# SMPS.net
KiCad netlist of a schematic drawn in Altium Designer
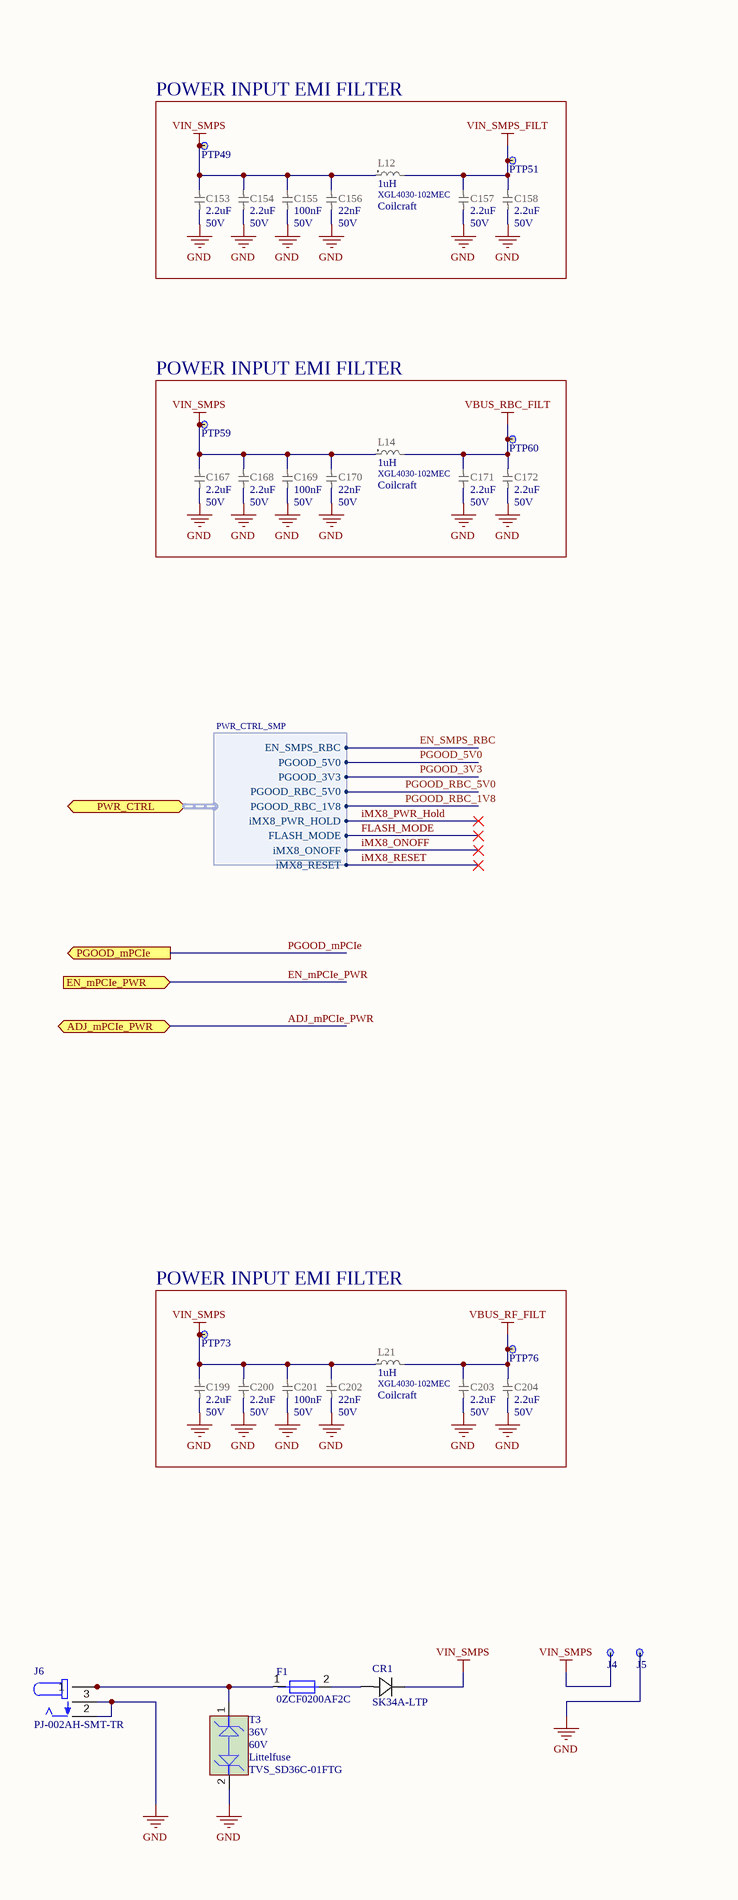
[diagram p0: SMPS.SchDoc, left]
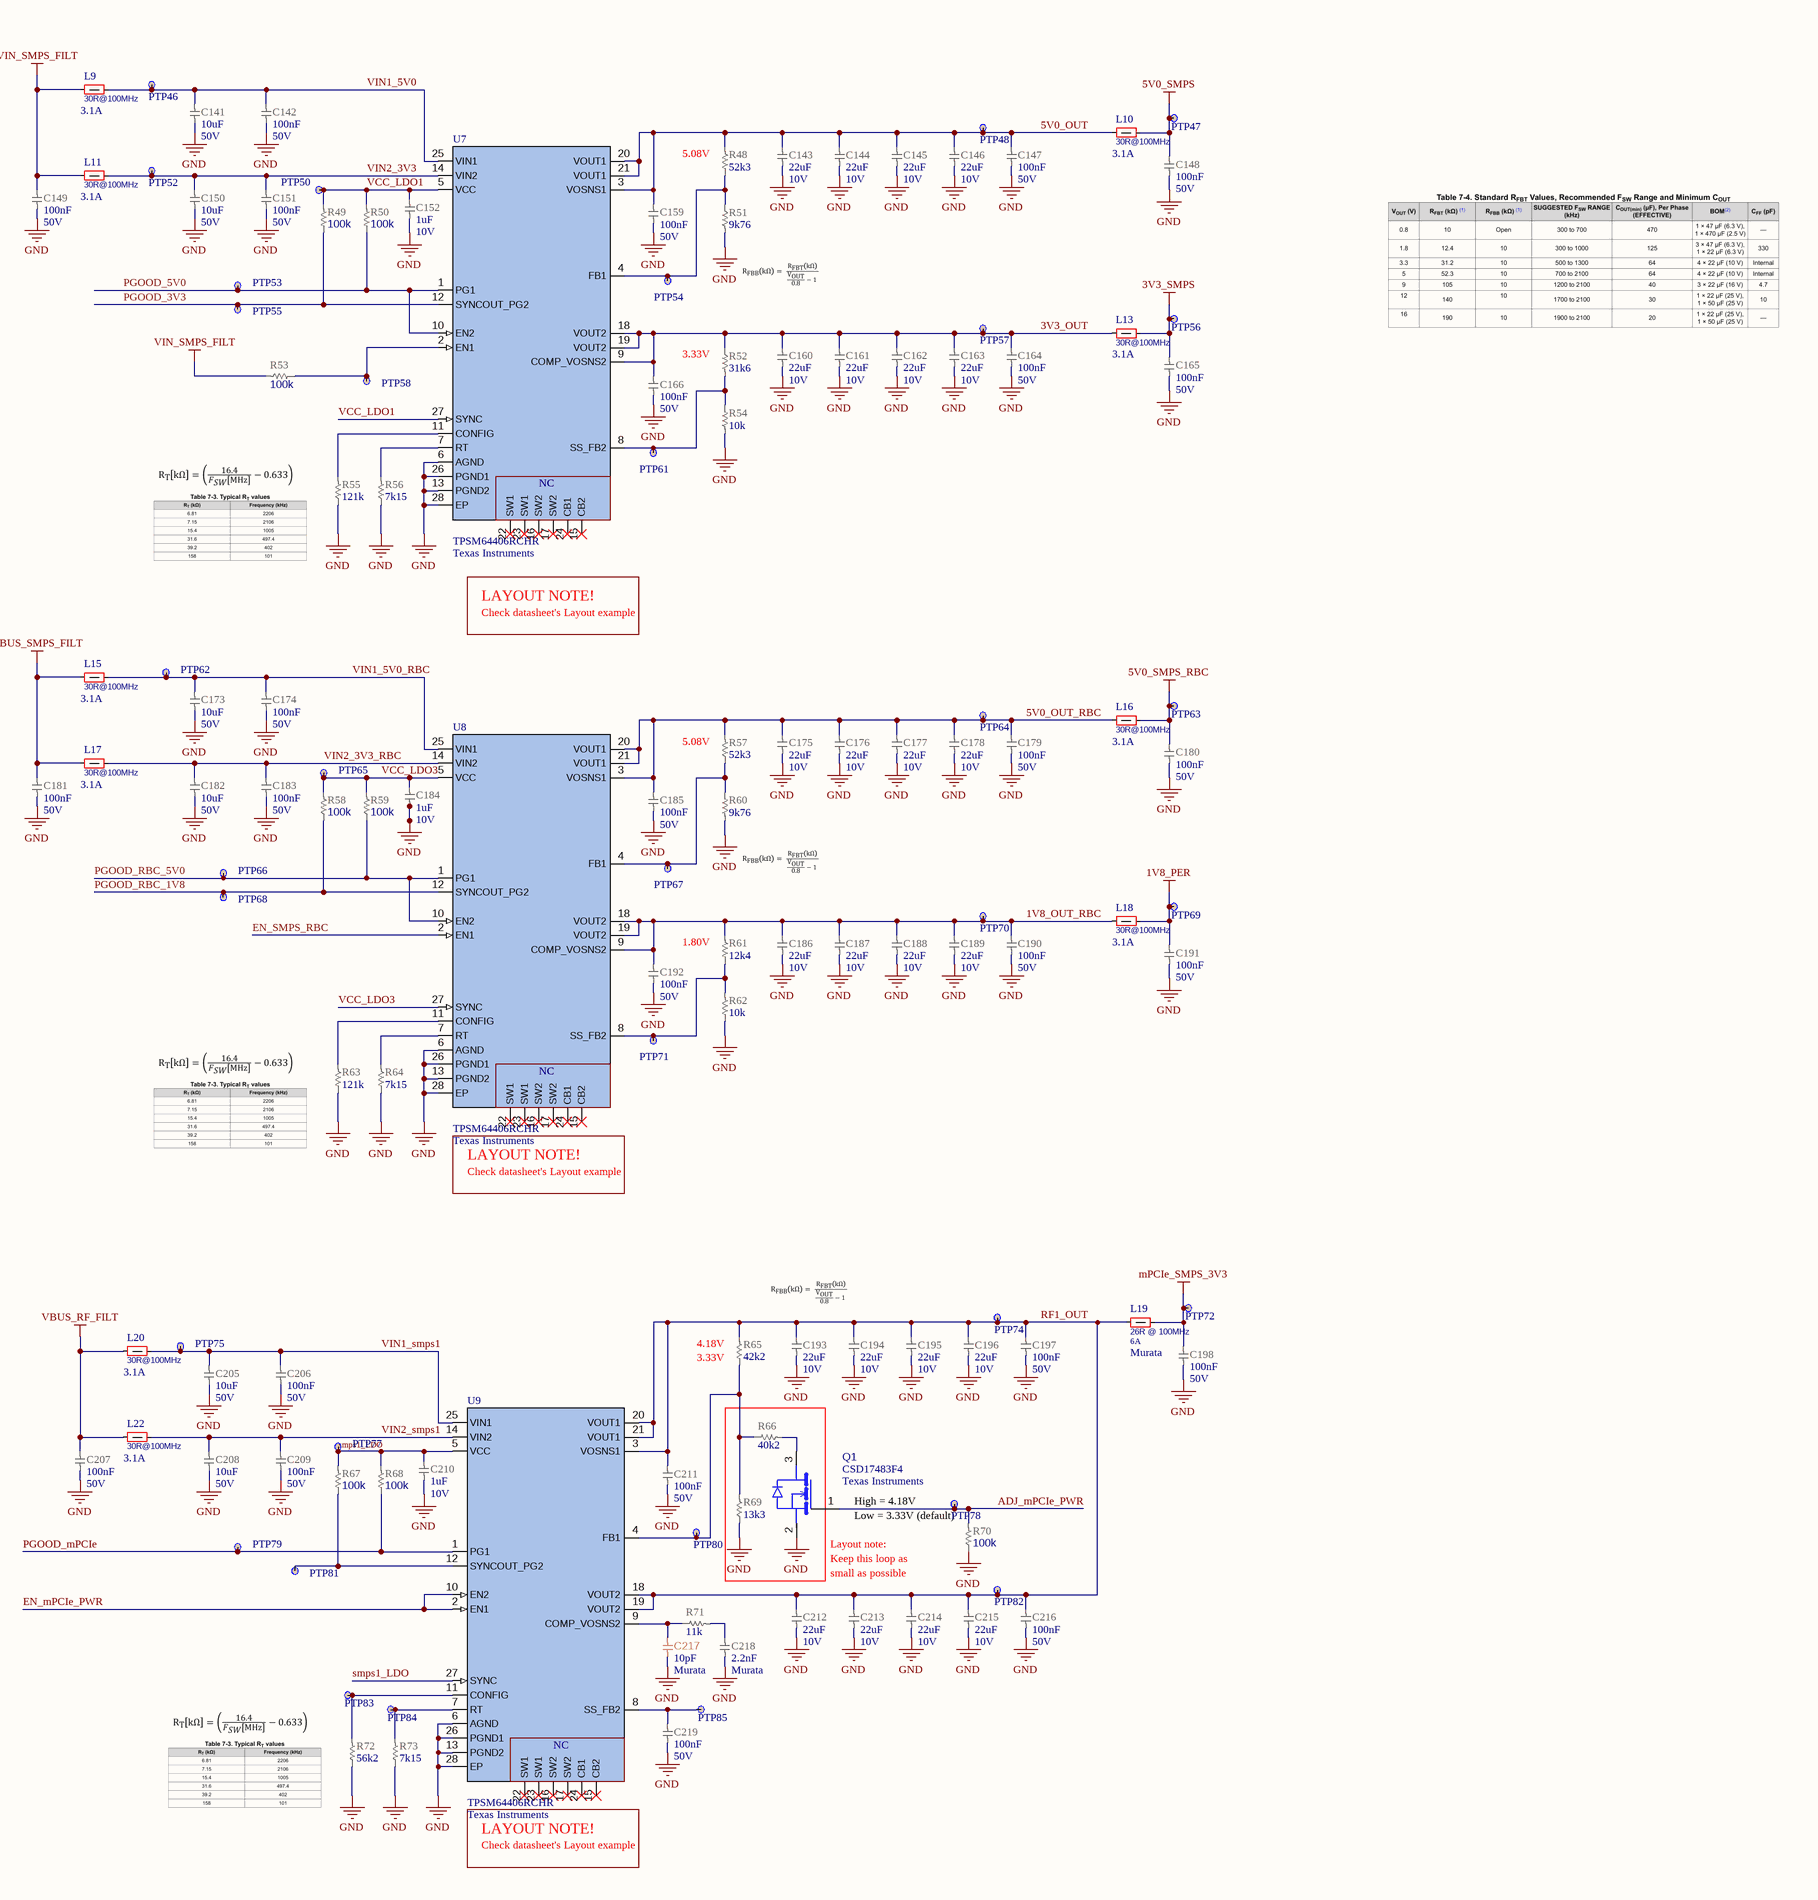
[diagram p1: SMPS.SchDoc, right]

(export (version "E")
  (design (tool "Eeschema 10.0.6"))
  (components
    (comp (ref "C141")
      (value "10uF")
      (footprint "CAP_1206_UN1Q")
      (description "CAP")
      (fields
        (field (name "PART NUMBER") "CL31B106KBHNNNE")
        (field (name "MANUFACTURER") "Samsung")
        (field (name "VOLTAGE") "50V")
      )
      (libsource (lib "robo_cam") (part "CMP-001-000368-12"))
    )
    (comp (ref "C142")
      (value "100nF")
      (footprint "CAP_0402_UN1Q")
      (description "CAP")
      (fields
        (field (name "PART NUMBER") "GRM155R71H104KE14D")
        (field (name "MANUFACTURER") "Murata")
        (field (name "VOLTAGE") "50V")
      )
      (libsource (lib "robo_cam") (part "CMP-001-000371-14"))
    )
    (comp (ref "C143")
      (value "22uF")
      (footprint "CAP_0805_UN1Q")
      (description "CAP")
      (fields
        (field (name "VOLTAGE") "10V")
        (field (name "TOLERANCE") "+/-20%")
        (field (name "PART NUMBER") "GRM21BZ71A226ME15L")
      )
      (libsource (lib "robo_cam") (part "CMP-001-000892-11"))
    )
    (comp (ref "C144")
      (value "22uF")
      (footprint "CAP_0805_UN1Q")
      (description "CAP")
      (fields
        (field (name "VOLTAGE") "10V")
        (field (name "TOLERANCE") "+/-20%")
        (field (name "PART NUMBER") "GRM21BZ71A226ME15L")
      )
      (libsource (lib "robo_cam") (part "CMP-001-000892-11"))
    )
    (comp (ref "C145")
      (value "22uF")
      (footprint "CAP_0805_UN1Q")
      (description "CAP")
      (fields
        (field (name "VOLTAGE") "10V")
        (field (name "TOLERANCE") "+/-20%")
        (field (name "PART NUMBER") "GRM21BZ71A226ME15L")
      )
      (libsource (lib "robo_cam") (part "CMP-001-000892-11"))
    )
    (comp (ref "C146")
      (value "22uF")
      (footprint "CAP_0805_UN1Q")
      (description "CAP")
      (fields
        (field (name "VOLTAGE") "10V")
        (field (name "TOLERANCE") "+/-20%")
        (field (name "PART NUMBER") "GRM21BZ71A226ME15L")
      )
      (libsource (lib "robo_cam") (part "CMP-001-000892-11"))
    )
    (comp (ref "C147")
      (value "100nF")
      (footprint "CAP_0402_UN1Q")
      (description "CAP")
      (fields
        (field (name "PART NUMBER") "GRM155R71H104KE14D")
        (field (name "MANUFACTURER") "Murata")
        (field (name "VOLTAGE") "50V")
      )
      (libsource (lib "robo_cam") (part "CMP-001-000371-14"))
    )
    (comp (ref "C148")
      (value "100nF")
      (footprint "CAP_0402_UN1Q")
      (description "CAP")
      (fields
        (field (name "PART NUMBER") "GRM155R71H104KE14D")
        (field (name "MANUFACTURER") "Murata")
        (field (name "VOLTAGE") "50V")
      )
      (libsource (lib "robo_cam") (part "CMP-001-000371-14"))
    )
    (comp (ref "C149")
      (value "100nF")
      (footprint "CAP_0402_UN1Q")
      (description "CAP")
      (fields
        (field (name "PART NUMBER") "GRM155R71H104KE14D")
        (field (name "MANUFACTURER") "Murata")
        (field (name "VOLTAGE") "50V")
      )
      (libsource (lib "robo_cam") (part "CMP-001-000371-14"))
    )
    (comp (ref "C150")
      (value "10uF")
      (footprint "CAP_1206_UN1Q")
      (description "CAP")
      (fields
        (field (name "PART NUMBER") "CL31B106KBHNNNE")
        (field (name "MANUFACTURER") "Samsung")
        (field (name "VOLTAGE") "50V")
      )
      (libsource (lib "robo_cam") (part "CMP-001-000368-12"))
    )
    (comp (ref "C151")
      (value "100nF")
      (footprint "CAP_0402_UN1Q")
      (description "CAP")
      (fields
        (field (name "PART NUMBER") "GRM155R71H104KE14D")
        (field (name "MANUFACTURER") "Murata")
        (field (name "VOLTAGE") "50V")
      )
      (libsource (lib "robo_cam") (part "CMP-001-000371-14"))
    )
    (comp (ref "C152")
      (value "1uF")
      (footprint "CAP_0201_UN1Q")
      (description "CAP")
      (fields
        (field (name "PART NUMBER") "KGM03CS61A105MH")
        (field (name "MANUFACTURER") "Kyocera")
        (field (name "VOLTAGE") "10V")
      )
      (libsource (lib "robo_cam") (part "CMP-001-000336-15"))
    )
    (comp (ref "C153")
      (value "2.2uF")
      (footprint "CAP_0805_UN1Q")
      (description "CAP")
      (fields
        (field (name "MANUFACTURER") "TDK")
        (field (name "PART NUMBER") "C2012X7R1H225K125AC")
        (field (name "VOLTAGE") "50V")
      )
      (libsource (lib "robo_cam") (part "CMP-001-000383-12"))
    )
    (comp (ref "C154")
      (value "2.2uF")
      (footprint "CAP_0805_UN1Q")
      (description "CAP")
      (fields
        (field (name "MANUFACTURER") "TDK")
        (field (name "PART NUMBER") "C2012X7R1H225K125AC")
        (field (name "VOLTAGE") "50V")
      )
      (libsource (lib "robo_cam") (part "CMP-001-000383-12"))
    )
    (comp (ref "C155")
      (value "100nF")
      (footprint "CAP_0402_UN1Q")
      (description "CAP")
      (fields
        (field (name "PART NUMBER") "GRM155R71H104KE14D")
        (field (name "MANUFACTURER") "Murata")
        (field (name "VOLTAGE") "50V")
      )
      (libsource (lib "robo_cam") (part "CMP-001-000371-14"))
    )
    (comp (ref "C156")
      (value "22nF")
      (footprint "CAP_0402_UN1Q")
      (description "CAP")
      (fields
        (field (name "VOLTAGE") "50V")
        (field (name "PART NUMBER") "GCM155R71H223KA55D")
        (field (name "TOLERANCE") "+/-10%")
      )
      (libsource (lib "robo_cam") (part "CMP-001-000321-12"))
    )
    (comp (ref "C157")
      (value "2.2uF")
      (footprint "CAP_0805_UN1Q")
      (description "CAP")
      (fields
        (field (name "MANUFACTURER") "TDK")
        (field (name "PART NUMBER") "C2012X7R1H225K125AC")
        (field (name "VOLTAGE") "50V")
      )
      (libsource (lib "robo_cam") (part "CMP-001-000383-12"))
    )
    (comp (ref "C158")
      (value "2.2uF")
      (footprint "CAP_0805_UN1Q")
      (description "CAP")
      (fields
        (field (name "MANUFACTURER") "TDK")
        (field (name "PART NUMBER") "C2012X7R1H225K125AC")
        (field (name "VOLTAGE") "50V")
      )
      (libsource (lib "robo_cam") (part "CMP-001-000383-12"))
    )
    (comp (ref "C159")
      (value "100nF")
      (footprint "CAP_0402_UN1Q")
      (description "CAP")
      (fields
        (field (name "PART NUMBER") "GRM155R71H104KE14D")
        (field (name "MANUFACTURER") "Murata")
        (field (name "VOLTAGE") "50V")
      )
      (libsource (lib "robo_cam") (part "CMP-001-000371-14"))
    )
    (comp (ref "C160")
      (value "22uF")
      (footprint "CAP_0805_UN1Q")
      (description "CAP")
      (fields
        (field (name "VOLTAGE") "10V")
        (field (name "TOLERANCE") "+/-20%")
        (field (name "PART NUMBER") "GRM21BZ71A226ME15L")
      )
      (libsource (lib "robo_cam") (part "CMP-001-000892-11"))
    )
    (comp (ref "C161")
      (value "22uF")
      (footprint "CAP_0805_UN1Q")
      (description "CAP")
      (fields
        (field (name "VOLTAGE") "10V")
        (field (name "TOLERANCE") "+/-20%")
        (field (name "PART NUMBER") "GRM21BZ71A226ME15L")
      )
      (libsource (lib "robo_cam") (part "CMP-001-000892-11"))
    )
    (comp (ref "C162")
      (value "22uF")
      (footprint "CAP_0805_UN1Q")
      (description "CAP")
      (fields
        (field (name "VOLTAGE") "10V")
        (field (name "TOLERANCE") "+/-20%")
        (field (name "PART NUMBER") "GRM21BZ71A226ME15L")
      )
      (libsource (lib "robo_cam") (part "CMP-001-000892-11"))
    )
    (comp (ref "C163")
      (value "22uF")
      (footprint "CAP_0805_UN1Q")
      (description "CAP")
      (fields
        (field (name "VOLTAGE") "10V")
        (field (name "TOLERANCE") "+/-20%")
        (field (name "PART NUMBER") "GRM21BZ71A226ME15L")
      )
      (libsource (lib "robo_cam") (part "CMP-001-000892-11"))
    )
    (comp (ref "C164")
      (value "100nF")
      (footprint "CAP_0402_UN1Q")
      (description "CAP")
      (fields
        (field (name "PART NUMBER") "GRM155R71H104KE14D")
        (field (name "MANUFACTURER") "Murata")
        (field (name "VOLTAGE") "50V")
      )
      (libsource (lib "robo_cam") (part "CMP-001-000371-14"))
    )
    (comp (ref "C165")
      (value "100nF")
      (footprint "CAP_0402_UN1Q")
      (description "CAP")
      (fields
        (field (name "PART NUMBER") "GRM155R71H104KE14D")
        (field (name "MANUFACTURER") "Murata")
        (field (name "VOLTAGE") "50V")
      )
      (libsource (lib "robo_cam") (part "CMP-001-000371-14"))
    )
    (comp (ref "C166")
      (value "100nF")
      (footprint "CAP_0402_UN1Q")
      (description "CAP")
      (fields
        (field (name "PART NUMBER") "GRM155R71H104KE14D")
        (field (name "MANUFACTURER") "Murata")
        (field (name "VOLTAGE") "50V")
      )
      (libsource (lib "robo_cam") (part "CMP-001-000371-14"))
    )
    (comp (ref "C167")
      (value "2.2uF")
      (footprint "CAP_0805_UN1Q")
      (description "CAP")
      (fields
        (field (name "MANUFACTURER") "TDK")
        (field (name "PART NUMBER") "C2012X7R1H225K125AC")
        (field (name "VOLTAGE") "50V")
      )
      (libsource (lib "robo_cam") (part "CMP-001-000383-12"))
    )
    (comp (ref "C168")
      (value "2.2uF")
      (footprint "CAP_0805_UN1Q")
      (description "CAP")
      (fields
        (field (name "MANUFACTURER") "TDK")
        (field (name "PART NUMBER") "C2012X7R1H225K125AC")
        (field (name "VOLTAGE") "50V")
      )
      (libsource (lib "robo_cam") (part "CMP-001-000383-12"))
    )
    (comp (ref "C169")
      (value "100nF")
      (footprint "CAP_0402_UN1Q")
      (description "CAP")
      (fields
        (field (name "PART NUMBER") "GRM155R71H104KE14D")
        (field (name "MANUFACTURER") "Murata")
        (field (name "VOLTAGE") "50V")
      )
      (libsource (lib "robo_cam") (part "CMP-001-000371-14"))
    )
    (comp (ref "C170")
      (value "22nF")
      (footprint "CAP_0402_UN1Q")
      (description "CAP")
      (fields
        (field (name "VOLTAGE") "50V")
        (field (name "PART NUMBER") "GCM155R71H223KA55D")
        (field (name "TOLERANCE") "+/-10%")
      )
      (libsource (lib "robo_cam") (part "CMP-001-000321-12"))
    )
    (comp (ref "C171")
      (value "2.2uF")
      (footprint "CAP_0805_UN1Q")
      (description "CAP")
      (fields
        (field (name "MANUFACTURER") "TDK")
        (field (name "PART NUMBER") "C2012X7R1H225K125AC")
        (field (name "VOLTAGE") "50V")
      )
      (libsource (lib "robo_cam") (part "CMP-001-000383-12"))
    )
    (comp (ref "C172")
      (value "2.2uF")
      (footprint "CAP_0805_UN1Q")
      (description "CAP")
      (fields
        (field (name "MANUFACTURER") "TDK")
        (field (name "PART NUMBER") "C2012X7R1H225K125AC")
        (field (name "VOLTAGE") "50V")
      )
      (libsource (lib "robo_cam") (part "CMP-001-000383-12"))
    )
    (comp (ref "C173")
      (value "10uF")
      (footprint "CAP_1206_UN1Q")
      (description "CAP")
      (fields
        (field (name "PART NUMBER") "CL31B106KBHNNNE")
        (field (name "MANUFACTURER") "Samsung")
        (field (name "VOLTAGE") "50V")
      )
      (libsource (lib "robo_cam") (part "CMP-001-000368-12"))
    )
    (comp (ref "C174")
      (value "100nF")
      (footprint "CAP_0402_UN1Q")
      (description "CAP")
      (fields
        (field (name "PART NUMBER") "GRM155R71H104KE14D")
        (field (name "MANUFACTURER") "Murata")
        (field (name "VOLTAGE") "50V")
      )
      (libsource (lib "robo_cam") (part "CMP-001-000371-14"))
    )
    (comp (ref "C175")
      (value "22uF")
      (footprint "CAP_0805_UN1Q")
      (description "CAP")
      (fields
        (field (name "VOLTAGE") "10V")
        (field (name "TOLERANCE") "+/-20%")
        (field (name "PART NUMBER") "GRM21BZ71A226ME15L")
      )
      (libsource (lib "robo_cam") (part "CMP-001-000892-11"))
    )
    (comp (ref "C176")
      (value "22uF")
      (footprint "CAP_0805_UN1Q")
      (description "CAP")
      (fields
        (field (name "VOLTAGE") "10V")
        (field (name "TOLERANCE") "+/-20%")
        (field (name "PART NUMBER") "GRM21BZ71A226ME15L")
      )
      (libsource (lib "robo_cam") (part "CMP-001-000892-11"))
    )
    (comp (ref "C177")
      (value "22uF")
      (footprint "CAP_0805_UN1Q")
      (description "CAP")
      (fields
        (field (name "VOLTAGE") "10V")
        (field (name "TOLERANCE") "+/-20%")
        (field (name "PART NUMBER") "GRM21BZ71A226ME15L")
      )
      (libsource (lib "robo_cam") (part "CMP-001-000892-11"))
    )
    (comp (ref "C178")
      (value "22uF")
      (footprint "CAP_0805_UN1Q")
      (description "CAP")
      (fields
        (field (name "VOLTAGE") "10V")
        (field (name "TOLERANCE") "+/-20%")
        (field (name "PART NUMBER") "GRM21BZ71A226ME15L")
      )
      (libsource (lib "robo_cam") (part "CMP-001-000892-11"))
    )
    (comp (ref "C179")
      (value "100nF")
      (footprint "CAP_0402_UN1Q")
      (description "CAP")
      (fields
        (field (name "PART NUMBER") "GRM155R71H104KE14D")
        (field (name "MANUFACTURER") "Murata")
        (field (name "VOLTAGE") "50V")
      )
      (libsource (lib "robo_cam") (part "CMP-001-000371-14"))
    )
    (comp (ref "C180")
      (value "100nF")
      (footprint "CAP_0402_UN1Q")
      (description "CAP")
      (fields
        (field (name "PART NUMBER") "GRM155R71H104KE14D")
        (field (name "MANUFACTURER") "Murata")
        (field (name "VOLTAGE") "50V")
      )
      (libsource (lib "robo_cam") (part "CMP-001-000371-14"))
    )
    (comp (ref "C181")
      (value "100nF")
      (footprint "CAP_0402_UN1Q")
      (description "CAP")
      (fields
        (field (name "PART NUMBER") "GRM155R71H104KE14D")
        (field (name "MANUFACTURER") "Murata")
        (field (name "VOLTAGE") "50V")
      )
      (libsource (lib "robo_cam") (part "CMP-001-000371-14"))
    )
    (comp (ref "C182")
      (value "10uF")
      (footprint "CAP_1206_UN1Q")
      (description "CAP")
      (fields
        (field (name "PART NUMBER") "CL31B106KBHNNNE")
        (field (name "MANUFACTURER") "Samsung")
        (field (name "VOLTAGE") "50V")
      )
      (libsource (lib "robo_cam") (part "CMP-001-000368-12"))
    )
    (comp (ref "C183")
      (value "100nF")
      (footprint "CAP_0402_UN1Q")
      (description "CAP")
      (fields
        (field (name "PART NUMBER") "GRM155R71H104KE14D")
        (field (name "MANUFACTURER") "Murata")
        (field (name "VOLTAGE") "50V")
      )
      (libsource (lib "robo_cam") (part "CMP-001-000371-14"))
    )
    (comp (ref "C184")
      (value "1uF")
      (footprint "CAP_0201_UN1Q")
      (description "CAP")
      (fields
        (field (name "PART NUMBER") "KGM03CS61A105MH")
        (field (name "MANUFACTURER") "Kyocera")
        (field (name "VOLTAGE") "10V")
      )
      (libsource (lib "robo_cam") (part "CMP-001-000336-15"))
    )
    (comp (ref "C185")
      (value "100nF")
      (footprint "CAP_0402_UN1Q")
      (description "CAP")
      (fields
        (field (name "PART NUMBER") "GRM155R71H104KE14D")
        (field (name "MANUFACTURER") "Murata")
        (field (name "VOLTAGE") "50V")
      )
      (libsource (lib "robo_cam") (part "CMP-001-000371-14"))
    )
    (comp (ref "C186")
      (value "22uF")
      (footprint "CAP_0805_UN1Q")
      (description "CAP")
      (fields
        (field (name "VOLTAGE") "10V")
        (field (name "TOLERANCE") "+/-20%")
        (field (name "PART NUMBER") "GRM21BZ71A226ME15L")
      )
      (libsource (lib "robo_cam") (part "CMP-001-000892-11"))
    )
    (comp (ref "C187")
      (value "22uF")
      (footprint "CAP_0805_UN1Q")
      (description "CAP")
      (fields
        (field (name "VOLTAGE") "10V")
        (field (name "TOLERANCE") "+/-20%")
        (field (name "PART NUMBER") "GRM21BZ71A226ME15L")
      )
      (libsource (lib "robo_cam") (part "CMP-001-000892-11"))
    )
    (comp (ref "C188")
      (value "22uF")
      (footprint "CAP_0805_UN1Q")
      (description "CAP")
      (fields
        (field (name "VOLTAGE") "10V")
        (field (name "TOLERANCE") "+/-20%")
        (field (name "PART NUMBER") "GRM21BZ71A226ME15L")
      )
      (libsource (lib "robo_cam") (part "CMP-001-000892-11"))
    )
    (comp (ref "C189")
      (value "22uF")
      (footprint "CAP_0805_UN1Q")
      (description "CAP")
      (fields
        (field (name "VOLTAGE") "10V")
        (field (name "TOLERANCE") "+/-20%")
        (field (name "PART NUMBER") "GRM21BZ71A226ME15L")
      )
      (libsource (lib "robo_cam") (part "CMP-001-000892-11"))
    )
    (comp (ref "C190")
      (value "100nF")
      (footprint "CAP_0402_UN1Q")
      (description "CAP")
      (fields
        (field (name "PART NUMBER") "GRM155R71H104KE14D")
        (field (name "MANUFACTURER") "Murata")
        (field (name "VOLTAGE") "50V")
      )
      (libsource (lib "robo_cam") (part "CMP-001-000371-14"))
    )
    (comp (ref "C191")
      (value "100nF")
      (footprint "CAP_0402_UN1Q")
      (description "CAP")
      (fields
        (field (name "PART NUMBER") "GRM155R71H104KE14D")
        (field (name "MANUFACTURER") "Murata")
        (field (name "VOLTAGE") "50V")
      )
      (libsource (lib "robo_cam") (part "CMP-001-000371-14"))
    )
    (comp (ref "C192")
      (value "100nF")
      (footprint "CAP_0402_UN1Q")
      (description "CAP")
      (fields
        (field (name "PART NUMBER") "GRM155R71H104KE14D")
        (field (name "MANUFACTURER") "Murata")
        (field (name "VOLTAGE") "50V")
      )
      (libsource (lib "robo_cam") (part "CMP-001-000371-14"))
    )
    (comp (ref "C193")
      (value "22uF")
      (footprint "CAP_0805_UN1Q")
      (description "CAP")
      (fields
        (field (name "VOLTAGE") "10V")
        (field (name "TOLERANCE") "+/-20%")
        (field (name "PART NUMBER") "GRM21BZ71A226ME15L")
      )
      (libsource (lib "robo_cam") (part "CMP-001-000892-11"))
    )
    (comp (ref "C194")
      (value "22uF")
      (footprint "CAP_0805_UN1Q")
      (description "CAP")
      (fields
        (field (name "VOLTAGE") "10V")
        (field (name "TOLERANCE") "+/-20%")
        (field (name "PART NUMBER") "GRM21BZ71A226ME15L")
      )
      (libsource (lib "robo_cam") (part "CMP-001-000892-11"))
    )
    (comp (ref "C195")
      (value "22uF")
      (footprint "CAP_0805_UN1Q")
      (description "CAP")
      (fields
        (field (name "VOLTAGE") "10V")
        (field (name "TOLERANCE") "+/-20%")
        (field (name "PART NUMBER") "GRM21BZ71A226ME15L")
      )
      (libsource (lib "robo_cam") (part "CMP-001-000892-11"))
    )
    (comp (ref "C196")
      (value "22uF")
      (footprint "CAP_0805_UN1Q")
      (description "CAP")
      (fields
        (field (name "VOLTAGE") "10V")
        (field (name "TOLERANCE") "+/-20%")
        (field (name "PART NUMBER") "GRM21BZ71A226ME15L")
      )
      (libsource (lib "robo_cam") (part "CMP-001-000892-11"))
    )
    (comp (ref "C197")
      (value "100nF")
      (footprint "CAP_0402_UN1Q")
      (description "CAP")
      (fields
        (field (name "PART NUMBER") "GRM155R71H104KE14D")
        (field (name "MANUFACTURER") "Murata")
        (field (name "VOLTAGE") "50V")
      )
      (libsource (lib "robo_cam") (part "CMP-001-000371-14"))
    )
    (comp (ref "C198")
      (value "100nF")
      (footprint "CAP_0402_UN1Q")
      (description "CAP")
      (fields
        (field (name "PART NUMBER") "GRM155R71H104KE14D")
        (field (name "MANUFACTURER") "Murata")
        (field (name "VOLTAGE") "50V")
      )
      (libsource (lib "robo_cam") (part "CMP-001-000371-14"))
    )
    (comp (ref "C199")
      (value "2.2uF")
      (footprint "CAP_0805_UN1Q")
      (description "CAP")
      (fields
        (field (name "MANUFACTURER") "TDK")
        (field (name "PART NUMBER") "C2012X7R1H225K125AC")
        (field (name "VOLTAGE") "50V")
      )
      (libsource (lib "robo_cam") (part "CMP-001-000383-12"))
    )
    (comp (ref "C200")
      (value "2.2uF")
      (footprint "CAP_0805_UN1Q")
      (description "CAP")
      (fields
        (field (name "MANUFACTURER") "TDK")
        (field (name "PART NUMBER") "C2012X7R1H225K125AC")
        (field (name "VOLTAGE") "50V")
      )
      (libsource (lib "robo_cam") (part "CMP-001-000383-12"))
    )
    (comp (ref "C201")
      (value "100nF")
      (footprint "CAP_0402_UN1Q")
      (description "CAP")
      (fields
        (field (name "PART NUMBER") "GRM155R71H104KE14D")
        (field (name "MANUFACTURER") "Murata")
        (field (name "VOLTAGE") "50V")
      )
      (libsource (lib "robo_cam") (part "CMP-001-000371-14"))
    )
    (comp (ref "C202")
      (value "22nF")
      (footprint "CAP_0402_UN1Q")
      (description "CAP")
      (fields
        (field (name "VOLTAGE") "50V")
        (field (name "PART NUMBER") "GCM155R71H223KA55D")
        (field (name "TOLERANCE") "+/-10%")
      )
      (libsource (lib "robo_cam") (part "CMP-001-000321-12"))
    )
    (comp (ref "C203")
      (value "2.2uF")
      (footprint "CAP_0805_UN1Q")
      (description "CAP")
      (fields
        (field (name "MANUFACTURER") "TDK")
        (field (name "PART NUMBER") "C2012X7R1H225K125AC")
        (field (name "VOLTAGE") "50V")
      )
      (libsource (lib "robo_cam") (part "CMP-001-000383-12"))
    )
    (comp (ref "C204")
      (value "2.2uF")
      (footprint "CAP_0805_UN1Q")
      (description "CAP")
      (fields
        (field (name "MANUFACTURER") "TDK")
        (field (name "PART NUMBER") "C2012X7R1H225K125AC")
        (field (name "VOLTAGE") "50V")
      )
      (libsource (lib "robo_cam") (part "CMP-001-000383-12"))
    )
    (comp (ref "C205")
      (value "10uF")
      (footprint "CAP_1206_UN1Q")
      (description "CAP")
      (fields
        (field (name "PART NUMBER") "CL31B106KBHNNNE")
        (field (name "MANUFACTURER") "Samsung")
        (field (name "VOLTAGE") "50V")
      )
      (libsource (lib "robo_cam") (part "CMP-001-000368-12"))
    )
    (comp (ref "C206")
      (value "100nF")
      (footprint "CAP_0402_UN1Q")
      (description "CAP")
      (fields
        (field (name "PART NUMBER") "GRM155R71H104KE14D")
        (field (name "MANUFACTURER") "Murata")
        (field (name "VOLTAGE") "50V")
      )
      (libsource (lib "robo_cam") (part "CMP-001-000371-14"))
    )
    (comp (ref "C207")
      (value "100nF")
      (footprint "CAP_0402_UN1Q")
      (description "CAP")
      (fields
        (field (name "PART NUMBER") "GRM155R71H104KE14D")
        (field (name "MANUFACTURER") "Murata")
        (field (name "VOLTAGE") "50V")
      )
      (libsource (lib "robo_cam") (part "CMP-001-000371-14"))
    )
    (comp (ref "C208")
      (value "10uF")
      (footprint "CAP_1206_UN1Q")
      (description "CAP")
      (fields
        (field (name "PART NUMBER") "CL31B106KBHNNNE")
        (field (name "MANUFACTURER") "Samsung")
        (field (name "VOLTAGE") "50V")
      )
      (libsource (lib "robo_cam") (part "CMP-001-000368-12"))
    )
    (comp (ref "C209")
      (value "100nF")
      (footprint "CAP_0402_UN1Q")
      (description "CAP")
      (fields
        (field (name "PART NUMBER") "GRM155R71H104KE14D")
        (field (name "MANUFACTURER") "Murata")
        (field (name "VOLTAGE") "50V")
      )
      (libsource (lib "robo_cam") (part "CMP-001-000371-14"))
    )
    (comp (ref "C210")
      (value "1uF")
      (footprint "CAP_0201_UN1Q")
      (description "CAP")
      (fields
        (field (name "PART NUMBER") "KGM03CS61A105MH")
        (field (name "MANUFACTURER") "Kyocera")
        (field (name "VOLTAGE") "10V")
      )
      (libsource (lib "robo_cam") (part "CMP-001-000336-15"))
    )
    (comp (ref "C211")
      (value "100nF")
      (footprint "CAP_0402_UN1Q")
      (description "CAP")
      (fields
        (field (name "PART NUMBER") "GRM155R71H104KE14D")
        (field (name "MANUFACTURER") "Murata")
        (field (name "VOLTAGE") "50V")
      )
      (libsource (lib "robo_cam") (part "CMP-001-000371-14"))
    )
    (comp (ref "C212")
      (value "22uF")
      (footprint "CAP_0805_UN1Q")
      (description "CAP")
      (fields
        (field (name "VOLTAGE") "10V")
        (field (name "TOLERANCE") "+/-20%")
        (field (name "PART NUMBER") "GRM21BZ71A226ME15L")
      )
      (libsource (lib "robo_cam") (part "CMP-001-000892-11"))
    )
    (comp (ref "C213")
      (value "22uF")
      (footprint "CAP_0805_UN1Q")
      (description "CAP")
      (fields
        (field (name "VOLTAGE") "10V")
        (field (name "TOLERANCE") "+/-20%")
        (field (name "PART NUMBER") "GRM21BZ71A226ME15L")
      )
      (libsource (lib "robo_cam") (part "CMP-001-000892-11"))
    )
    (comp (ref "C214")
      (value "22uF")
      (footprint "CAP_0805_UN1Q")
      (description "CAP")
      (fields
        (field (name "VOLTAGE") "10V")
        (field (name "TOLERANCE") "+/-20%")
        (field (name "PART NUMBER") "GRM21BZ71A226ME15L")
      )
      (libsource (lib "robo_cam") (part "CMP-001-000892-11"))
    )
    (comp (ref "C215")
      (value "22uF")
      (footprint "CAP_0805_UN1Q")
      (description "CAP")
      (fields
        (field (name "VOLTAGE") "10V")
        (field (name "TOLERANCE") "+/-20%")
        (field (name "PART NUMBER") "GRM21BZ71A226ME15L")
      )
      (libsource (lib "robo_cam") (part "CMP-001-000892-11"))
    )
    (comp (ref "C216")
      (value "100nF")
      (footprint "CAP_0402_UN1Q")
      (description "CAP")
      (fields
        (field (name "PART NUMBER") "GRM155R71H104KE14D")
        (field (name "MANUFACTURER") "Murata")
        (field (name "VOLTAGE") "50V")
      )
      (libsource (lib "robo_cam") (part "CMP-001-000371-14"))
    )
    (comp (ref "C217")
      (value "10pF")
      (footprint "CAP_0201_UN1Q")
      (description "CAP_RF_MATCHING")
      (fields
        (field (name "PART NUMBER") "GJM0335C1E100GB01D")
        (field (name "MANUFACTURER") "Murata")
        (field (name "MANUFACTURER_1") "Murata")
      )
      (libsource (lib "CM5_library") (part "CMP-001-000419-13"))
    )
    (comp (ref "C218")
      (value "2.2nF")
      (footprint "CAP_0201_UN1Q")
      (description "CAP")
      (fields
        (field (name "PART NUMBER") "GRM033R71E222KA12J")
        (field (name "MANUFACTURER") "Murata")
        (field (name "MANUFACTURER_1") "Murata")
      )
      (libsource (lib "CM5_library") (part "CMP-001-000281-14"))
    )
    (comp (ref "C219")
      (value "100nF")
      (footprint "CAP_0402_UN1Q")
      (description "CAP")
      (fields
        (field (name "PART NUMBER") "GRM155R71H104KE14D")
        (field (name "MANUFACTURER") "Murata")
        (field (name "VOLTAGE") "50V")
      )
      (libsource (lib "robo_cam") (part "CMP-001-000371-14"))
    )
    (comp (ref "CR1")
      (value "SK34A-LTP")
      (footprint "SMADO-214AC_MCC")
      (description "Description")
      (fields (field (name "COPYRIGHT") "Copyright (C) 2025 Ultra Librarian. All rights reserved."))
      (libsource (lib "SK34A-LTP") (part "SK34A-LTP"))
    )
    (comp (ref "F1")
      (value "0ZCF0200AF2C")
      (footprint "FUSE_0ZCF0075AF2C")
      (description "2920 SMT PPTC ¦ 2.00 Ih ¦ 24V")
      (fields (field (name "MF") "Bel Fuse") (field (name "DIGI-KEY_PART_NUMBER") "507-1749-2-ND"))
      (libsource (lib "0ZCF0200AF2C") (part "0ZCF0200AF2C"))
    )
    (comp (ref "J4")
      (value "PAD 1 x 2 mm")
      (footprint "TP_1x2mm_UN1Q")
      (fields (field (name "PART NUMBER") "TP 1x2mm"))
      (libsource (lib "robo_cam") (part "CMP-001-000157-12"))
    )
    (comp (ref "J5")
      (value "PAD 1 x 2 mm")
      (footprint "TP_1x2mm_UN1Q")
      (fields (field (name "PART NUMBER") "TP 1x2mm"))
      (libsource (lib "robo_cam") (part "CMP-001-000157-12"))
    )
    (comp (ref "J6")
      (value "PJ-002AH-SMT-TR")
      (footprint "CUI_PJ-002AH-SMT-TR")
      (description "2.0 x 6.5 mm, 5.0 A, Horizontal, Surface Mount (SMT), Dc Power Jack Connector")
      (fields (field (name "MF") "Same Sky"))
      (libsource (lib "PJ-002AH-SMT-TR") (part "PJ-002AH-SMT-TR"))
    )
    (comp (ref "L9")
      (value "30R@100MHz")
      (footprint "FERR_BLM15KD")
      (description "FERRITE")
      (fields
        (field (name "PART NUMBER") "BLM15KD300SN1")
        (field (name "MANUFACTURER") "Murata")
        (field (name "CURRENT") "3.1A")
      )
      (libsource (lib "robo_cam") (part "CMP-001-000738-12"))
    )
    (comp (ref "L10")
      (value "30R@100MHz")
      (footprint "FERR_BLM15KD")
      (description "FERRITE")
      (fields
        (field (name "PART NUMBER") "BLM15KD300SN1")
        (field (name "MANUFACTURER") "Murata")
        (field (name "CURRENT") "3.1A")
      )
      (libsource (lib "robo_cam") (part "CMP-001-000738-12"))
    )
    (comp (ref "L11")
      (value "30R@100MHz")
      (footprint "FERR_BLM15KD")
      (description "FERRITE")
      (fields
        (field (name "PART NUMBER") "BLM15KD300SN1")
        (field (name "MANUFACTURER") "Murata")
        (field (name "CURRENT") "3.1A")
      )
      (libsource (lib "robo_cam") (part "CMP-001-000738-12"))
    )
    (comp (ref "L12")
      (value "1uH")
      (footprint "IND_XGL4030")
      (description "IND, Low DCR, shielded.")
      (fields
        (field (name "PART NUMBER") "XGL4030-102MEC")
        (field (name "MANUFACTURER") "Coilcraft")
        (field (name "MANUFACTURER_1") "Coilcraft")
        (field (name "MANUFACTURER PART NUMBER") "XGL4030-102MEC")
      )
      (libsource (lib "robo_cam") (part "CMP-001-001158-1"))
    )
    (comp (ref "L13")
      (value "30R@100MHz")
      (footprint "FERR_BLM15KD")
      (description "FERRITE")
      (fields
        (field (name "PART NUMBER") "BLM15KD300SN1")
        (field (name "MANUFACTURER") "Murata")
        (field (name "CURRENT") "3.1A")
      )
      (libsource (lib "robo_cam") (part "CMP-001-000738-12"))
    )
    (comp (ref "L14")
      (value "1uH")
      (footprint "IND_XGL4030")
      (description "IND, Low DCR, shielded.")
      (fields
        (field (name "PART NUMBER") "XGL4030-102MEC")
        (field (name "MANUFACTURER") "Coilcraft")
        (field (name "MANUFACTURER_1") "Coilcraft")
        (field (name "MANUFACTURER PART NUMBER") "XGL4030-102MEC")
      )
      (libsource (lib "robo_cam") (part "CMP-001-001158-1"))
    )
    (comp (ref "L15")
      (value "30R@100MHz")
      (footprint "FERR_BLM15KD")
      (description "FERRITE")
      (fields
        (field (name "PART NUMBER") "BLM15KD300SN1")
        (field (name "MANUFACTURER") "Murata")
        (field (name "CURRENT") "3.1A")
      )
      (libsource (lib "robo_cam") (part "CMP-001-000738-12"))
    )
    (comp (ref "L16")
      (value "30R@100MHz")
      (footprint "FERR_BLM15KD")
      (description "FERRITE")
      (fields
        (field (name "PART NUMBER") "BLM15KD300SN1")
        (field (name "MANUFACTURER") "Murata")
        (field (name "CURRENT") "3.1A")
      )
      (libsource (lib "robo_cam") (part "CMP-001-000738-12"))
    )
    (comp (ref "L17")
      (value "30R@100MHz")
      (footprint "FERR_BLM15KD")
      (description "FERRITE")
      (fields
        (field (name "PART NUMBER") "BLM15KD300SN1")
        (field (name "MANUFACTURER") "Murata")
        (field (name "CURRENT") "3.1A")
      )
      (libsource (lib "robo_cam") (part "CMP-001-000738-12"))
    )
    (comp (ref "L18")
      (value "30R@100MHz")
      (footprint "FERR_BLM15KD")
      (description "FERRITE")
      (fields
        (field (name "PART NUMBER") "BLM15KD300SN1")
        (field (name "MANUFACTURER") "Murata")
        (field (name "CURRENT") "3.1A")
      )
      (libsource (lib "robo_cam") (part "CMP-001-000738-12"))
    )
    (comp (ref "L19")
      (value "26R @ 100MHz")
      (footprint "IND_0603_UN1Q")
      (description "FERRITE")
      (fields
        (field (name "MANUFACTURER") "Murata")
        (field (name "PART NUMBER") "BLM18KG260TN1")
        (field (name "CURRENT") "6A")
        (field (name "MANUFACTURER_1") "Murata")
      )
      (libsource (lib "CM5_library") (part "CMP-001-000740-8"))
    )
    (comp (ref "L20")
      (value "30R@100MHz")
      (footprint "FERR_BLM15KD")
      (description "FERRITE")
      (fields
        (field (name "PART NUMBER") "BLM15KD300SN1")
        (field (name "MANUFACTURER") "Murata")
        (field (name "CURRENT") "3.1A")
      )
      (libsource (lib "robo_cam") (part "CMP-001-000738-12"))
    )
    (comp (ref "L21")
      (value "1uH")
      (footprint "IND_XGL4030")
      (description "IND, Low DCR, shielded.")
      (fields
        (field (name "PART NUMBER") "XGL4030-102MEC")
        (field (name "MANUFACTURER") "Coilcraft")
        (field (name "MANUFACTURER_1") "Coilcraft")
        (field (name "MANUFACTURER PART NUMBER") "XGL4030-102MEC")
      )
      (libsource (lib "robo_cam") (part "CMP-001-001158-1"))
    )
    (comp (ref "L22")
      (value "30R@100MHz")
      (footprint "FERR_BLM15KD")
      (description "FERRITE")
      (fields
        (field (name "PART NUMBER") "BLM15KD300SN1")
        (field (name "MANUFACTURER") "Murata")
        (field (name "CURRENT") "3.1A")
      )
      (libsource (lib "robo_cam") (part "CMP-001-000738-12"))
    )
    (comp (ref "PTP46")
      (value "PTP_0.4mm")
      (footprint "PTP_0.4mm")
      (description "Production Testpoint 0.4mm. Flying probe. Use 1mm pitch.")
      (fields (field (name "PART NUMBER") "PTP 0.4mm"))
      (libsource (lib "robo_cam") (part "CMP-001-001296-3"))
    )
    (comp (ref "PTP47")
      (value "PTP_0.4mm")
      (footprint "PTP_0.4mm")
      (description "Production Testpoint 0.4mm. Flying probe. Use 1mm pitch.")
      (fields (field (name "PART NUMBER") "PTP 0.4mm"))
      (libsource (lib "robo_cam") (part "CMP-001-001296-3"))
    )
    (comp (ref "PTP48")
      (value "PTP_0.4mm")
      (footprint "PTP_0.4mm")
      (description "Production Testpoint 0.4mm. Flying probe. Use 1mm pitch.")
      (fields (field (name "PART NUMBER") "PTP 0.4mm"))
      (libsource (lib "robo_cam") (part "CMP-001-001296-3"))
    )
    (comp (ref "PTP49")
      (value "PTP_0.4mm")
      (footprint "PTP_0.4mm")
      (description "Production Testpoint 0.4mm. Flying probe. Use 1mm pitch.")
      (fields (field (name "PART NUMBER") "PTP 0.4mm"))
      (libsource (lib "robo_cam") (part "CMP-001-001296-3"))
    )
    (comp (ref "PTP50")
      (value "PTP_0.4mm")
      (footprint "PTP_0.4mm")
      (description "Production Testpoint 0.4mm. Flying probe. Use 1mm pitch.")
      (fields (field (name "PART NUMBER") "PTP 0.4mm"))
      (libsource (lib "robo_cam") (part "CMP-001-001296-3"))
    )
    (comp (ref "PTP51")
      (value "PTP_0.4mm")
      (footprint "PTP_0.4mm")
      (description "Production Testpoint 0.4mm. Flying probe. Use 1mm pitch.")
      (fields (field (name "PART NUMBER") "PTP 0.4mm"))
      (libsource (lib "robo_cam") (part "CMP-001-001296-3"))
    )
    (comp (ref "PTP52")
      (value "PTP_0.4mm")
      (footprint "PTP_0.4mm")
      (description "Production Testpoint 0.4mm. Flying probe. Use 1mm pitch.")
      (fields (field (name "PART NUMBER") "PTP 0.4mm"))
      (libsource (lib "robo_cam") (part "CMP-001-001296-3"))
    )
    (comp (ref "PTP53")
      (value "PTP_0.4mm")
      (footprint "PTP_0.4mm")
      (description "Production Testpoint 0.4mm. Flying probe. Use 1mm pitch.")
      (fields (field (name "PART NUMBER") "PTP 0.4mm"))
      (libsource (lib "robo_cam") (part "CMP-001-001296-3"))
    )
    (comp (ref "PTP54")
      (value "PTP_0.4mm")
      (footprint "PTP_0.4mm")
      (description "Production Testpoint 0.4mm. Flying probe. Use 1mm pitch.")
      (fields (field (name "PART NUMBER") "PTP 0.4mm"))
      (libsource (lib "robo_cam") (part "CMP-001-001296-3"))
    )
    (comp (ref "PTP55")
      (value "PTP_0.4mm")
      (footprint "PTP_0.4mm")
      (description "Production Testpoint 0.4mm. Flying probe. Use 1mm pitch.")
      (fields (field (name "PART NUMBER") "PTP 0.4mm"))
      (libsource (lib "robo_cam") (part "CMP-001-001296-3"))
    )
    (comp (ref "PTP56")
      (value "PTP_0.4mm")
      (footprint "PTP_0.4mm")
      (description "Production Testpoint 0.4mm. Flying probe. Use 1mm pitch.")
      (fields (field (name "PART NUMBER") "PTP 0.4mm"))
      (libsource (lib "robo_cam") (part "CMP-001-001296-3"))
    )
    (comp (ref "PTP57")
      (value "PTP_0.4mm")
      (footprint "PTP_0.4mm")
      (description "Production Testpoint 0.4mm. Flying probe. Use 1mm pitch.")
      (fields (field (name "PART NUMBER") "PTP 0.4mm"))
      (libsource (lib "robo_cam") (part "CMP-001-001296-3"))
    )
    (comp (ref "PTP58")
      (value "PTP_0.4mm")
      (footprint "PTP_0.4mm")
      (description "Production Testpoint 0.4mm. Flying probe. Use 1mm pitch.")
      (fields (field (name "PART NUMBER") "PTP 0.4mm"))
      (libsource (lib "robo_cam") (part "CMP-001-001296-3"))
    )
    (comp (ref "PTP59")
      (value "PTP_0.4mm")
      (footprint "PTP_0.4mm")
      (description "Production Testpoint 0.4mm. Flying probe. Use 1mm pitch.")
      (fields (field (name "PART NUMBER") "PTP 0.4mm"))
      (libsource (lib "robo_cam") (part "CMP-001-001296-3"))
    )
    (comp (ref "PTP60")
      (value "PTP_0.4mm")
      (footprint "PTP_0.4mm")
      (description "Production Testpoint 0.4mm. Flying probe. Use 1mm pitch.")
      (fields (field (name "PART NUMBER") "PTP 0.4mm"))
      (libsource (lib "robo_cam") (part "CMP-001-001296-3"))
    )
    (comp (ref "PTP61")
      (value "PTP_0.4mm")
      (footprint "PTP_0.4mm")
      (description "Production Testpoint 0.4mm. Flying probe. Use 1mm pitch.")
      (fields (field (name "PART NUMBER") "PTP 0.4mm"))
      (libsource (lib "robo_cam") (part "CMP-001-001296-3"))
    )
    (comp (ref "PTP62")
      (value "PTP_0.4mm")
      (footprint "PTP_0.4mm")
      (description "Production Testpoint 0.4mm. Flying probe. Use 1mm pitch.")
      (fields (field (name "PART NUMBER") "PTP 0.4mm"))
      (libsource (lib "robo_cam") (part "CMP-001-001296-3"))
    )
    (comp (ref "PTP63")
      (value "PTP_0.4mm")
      (footprint "PTP_0.4mm")
      (description "Production Testpoint 0.4mm. Flying probe. Use 1mm pitch.")
      (fields (field (name "PART NUMBER") "PTP 0.4mm"))
      (libsource (lib "robo_cam") (part "CMP-001-001296-3"))
    )
    (comp (ref "PTP64")
      (value "PTP_0.4mm")
      (footprint "PTP_0.4mm")
      (description "Production Testpoint 0.4mm. Flying probe. Use 1mm pitch.")
      (fields (field (name "PART NUMBER") "PTP 0.4mm"))
      (libsource (lib "robo_cam") (part "CMP-001-001296-3"))
    )
    (comp (ref "PTP65")
      (value "PTP_0.4mm")
      (footprint "PTP_0.4mm")
      (description "Production Testpoint 0.4mm. Flying probe. Use 1mm pitch.")
      (fields (field (name "PART NUMBER") "PTP 0.4mm"))
      (libsource (lib "robo_cam") (part "CMP-001-001296-3"))
    )
    (comp (ref "PTP66")
      (value "PTP_0.4mm")
      (footprint "PTP_0.4mm")
      (description "Production Testpoint 0.4mm. Flying probe. Use 1mm pitch.")
      (fields (field (name "PART NUMBER") "PTP 0.4mm"))
      (libsource (lib "robo_cam") (part "CMP-001-001296-3"))
    )
    (comp (ref "PTP67")
      (value "PTP_0.4mm")
      (footprint "PTP_0.4mm")
      (description "Production Testpoint 0.4mm. Flying probe. Use 1mm pitch.")
      (fields (field (name "PART NUMBER") "PTP 0.4mm"))
      (libsource (lib "robo_cam") (part "CMP-001-001296-3"))
    )
    (comp (ref "PTP68")
      (value "PTP_0.4mm")
      (footprint "PTP_0.4mm")
      (description "Production Testpoint 0.4mm. Flying probe. Use 1mm pitch.")
      (fields (field (name "PART NUMBER") "PTP 0.4mm"))
      (libsource (lib "robo_cam") (part "CMP-001-001296-3"))
    )
    (comp (ref "PTP69")
      (value "PTP_0.4mm")
      (footprint "PTP_0.4mm")
      (description "Production Testpoint 0.4mm. Flying probe. Use 1mm pitch.")
      (fields (field (name "PART NUMBER") "PTP 0.4mm"))
      (libsource (lib "robo_cam") (part "CMP-001-001296-3"))
    )
    (comp (ref "PTP70")
      (value "PTP_0.4mm")
      (footprint "PTP_0.4mm")
      (description "Production Testpoint 0.4mm. Flying probe. Use 1mm pitch.")
      (fields (field (name "PART NUMBER") "PTP 0.4mm"))
      (libsource (lib "robo_cam") (part "CMP-001-001296-3"))
    )
    (comp (ref "PTP71")
      (value "PTP_0.4mm")
      (footprint "PTP_0.4mm")
      (description "Production Testpoint 0.4mm. Flying probe. Use 1mm pitch.")
      (fields (field (name "PART NUMBER") "PTP 0.4mm"))
      (libsource (lib "robo_cam") (part "CMP-001-001296-3"))
    )
    (comp (ref "PTP72")
      (value "PTP_0.4mm")
      (footprint "PTP_0.4mm")
      (description "Production Testpoint 0.4mm. Flying probe. Use 1mm pitch.")
      (fields (field (name "PART NUMBER") "PTP 0.4mm"))
      (libsource (lib "robo_cam") (part "CMP-001-001296-3"))
    )
    (comp (ref "PTP73")
      (value "PTP_0.4mm")
      (footprint "PTP_0.4mm")
      (description "Production Testpoint 0.4mm. Flying probe. Use 1mm pitch.")
      (fields (field (name "PART NUMBER") "PTP 0.4mm"))
      (libsource (lib "robo_cam") (part "CMP-001-001296-3"))
    )
    (comp (ref "PTP74")
      (value "PTP_0.4mm")
      (footprint "PTP_0.4mm")
      (description "Production Testpoint 0.4mm. Flying probe. Use 1mm pitch.")
      (fields (field (name "PART NUMBER") "PTP 0.4mm"))
      (libsource (lib "robo_cam") (part "CMP-001-001296-3"))
    )
    (comp (ref "PTP75")
      (value "PTP_0.4mm")
      (footprint "PTP_0.4mm")
      (description "Production Testpoint 0.4mm. Flying probe. Use 1mm pitch.")
      (fields (field (name "PART NUMBER") "PTP 0.4mm"))
      (libsource (lib "robo_cam") (part "CMP-001-001296-3"))
    )
    (comp (ref "PTP76")
      (value "PTP_0.4mm")
      (footprint "PTP_0.4mm")
      (description "Production Testpoint 0.4mm. Flying probe. Use 1mm pitch.")
      (fields (field (name "PART NUMBER") "PTP 0.4mm"))
      (libsource (lib "robo_cam") (part "CMP-001-001296-3"))
    )
    (comp (ref "PTP77")
      (value "PTP_0.4mm")
      (footprint "PTP_0.4mm")
      (description "Production Testpoint 0.4mm. Flying probe. Use 1mm pitch.")
      (fields (field (name "PART NUMBER") "PTP 0.4mm"))
      (libsource (lib "robo_cam") (part "CMP-001-001296-3"))
    )
    (comp (ref "PTP78")
      (value "PTP_0.4mm")
      (footprint "PTP_0.4mm")
      (description "Production Testpoint 0.4mm. Flying probe. Use 1mm pitch.")
      (fields (field (name "PART NUMBER") "PTP 0.4mm"))
      (libsource (lib "robo_cam") (part "CMP-001-001296-3"))
    )
    (comp (ref "PTP79")
      (value "PTP_0.4mm")
      (footprint "PTP_0.4mm")
      (description "Production Testpoint 0.4mm. Flying probe. Use 1mm pitch.")
      (fields (field (name "PART NUMBER") "PTP 0.4mm"))
      (libsource (lib "robo_cam") (part "CMP-001-001296-3"))
    )
    (comp (ref "PTP80")
      (value "PTP_0.4mm")
      (footprint "PTP_0.4mm")
      (description "Production Testpoint 0.4mm. Flying probe. Use 1mm pitch.")
      (fields (field (name "PART NUMBER") "PTP 0.4mm"))
      (libsource (lib "robo_cam") (part "CMP-001-001296-3"))
    )
    (comp (ref "PTP81")
      (value "PTP_0.4mm")
      (footprint "PTP_0.4mm")
      (description "Production Testpoint 0.4mm. Flying probe. Use 1mm pitch.")
      (fields (field (name "PART NUMBER") "PTP 0.4mm"))
      (libsource (lib "robo_cam") (part "CMP-001-001296-3"))
    )
    (comp (ref "PTP82")
      (value "PTP_0.4mm")
      (footprint "PTP_0.4mm")
      (description "Production Testpoint 0.4mm. Flying probe. Use 1mm pitch.")
      (fields (field (name "PART NUMBER") "PTP 0.4mm"))
      (libsource (lib "robo_cam") (part "CMP-001-001296-3"))
    )
    (comp (ref "PTP83")
      (value "PTP_0.4mm")
      (footprint "PTP_0.4mm")
      (description "Production Testpoint 0.4mm. Flying probe. Use 1mm pitch.")
      (fields (field (name "PART NUMBER") "PTP 0.4mm"))
      (libsource (lib "robo_cam") (part "CMP-001-001296-3"))
    )
    (comp (ref "PTP84")
      (value "PTP_0.4mm")
      (footprint "PTP_0.4mm")
      (description "Production Testpoint 0.4mm. Flying probe. Use 1mm pitch.")
      (fields (field (name "PART NUMBER") "PTP 0.4mm"))
      (libsource (lib "robo_cam") (part "CMP-001-001296-3"))
    )
    (comp (ref "PTP85")
      (value "PTP_0.4mm")
      (footprint "PTP_0.4mm")
      (description "Production Testpoint 0.4mm. Flying probe. Use 1mm pitch.")
      (fields (field (name "PART NUMBER") "PTP 0.4mm"))
      (libsource (lib "robo_cam") (part "CMP-001-001296-3"))
    )
    (comp (ref "Q1")
      (value "CSD17483F4")
      (footprint "3-PICOSTAR_TI")
      (description "NMOS Transistor, 30V, 1.5A, 260mOhm")
      (fields
        (field (name "MANUFACTURER") "TI")
        (field (name "PART NUMBER") "CSD17483F4")
        (field (name "MANUFACTURER_1") "Texas Instruments")
      )
      (libsource (lib "CM5_library") (part "CMP-001-001632-2"))
    )
    (comp (ref "R48")
      (value "52k3")
      (footprint "RES_0201_UN1Q")
      (description "RES")
      (fields (field (name "TOLERANCE") "1%") (field (name "MANUFACTURER") "YAGEO"))
      (libsource (lib "robo_cam") (part "CMP-001-001154-3"))
    )
    (comp (ref "R49")
      (value "100k")
      (footprint "RES_0201_UN1Q")
      (description "RES")
      (fields (field (name "TOLERANCE") "1%") (field (name "PART NUMBER") "RC0201FR-07100KL"))
      (libsource (lib "robo_cam") (part "CMP-001-000526-11"))
    )
    (comp (ref "R50")
      (value "100k")
      (footprint "RES_0201_UN1Q")
      (description "RES")
      (fields (field (name "TOLERANCE") "1%") (field (name "PART NUMBER") "RC0201FR-07100KL"))
      (libsource (lib "robo_cam") (part "CMP-001-000526-11"))
    )
    (comp (ref "R51")
      (value "9k76")
      (footprint "RES_0201_UN1Q")
      (description "RES")
      (fields (field (name "PART NUMBER") "RC0201FR-079K76L") (field (name "TOLERANCE") "1%"))
      (libsource (lib "robo_cam") (part "CMP-001-001155-2"))
    )
    (comp (ref "R52")
      (value "31k6")
      (footprint "RES_0201_UN1Q")
      (description "RES")
      (fields (field (name "TOLERANCE") "1%") (field (name "MANUFACTURER") "YAGEO"))
      (libsource (lib "robo_cam") (part "CMP-001-001153-3"))
    )
    (comp (ref "R53")
      (value "100k")
      (footprint "RES_0201_UN1Q")
      (description "RES")
      (fields (field (name "TOLERANCE") "1%") (field (name "PART NUMBER") "RC0201FR-07100KL"))
      (libsource (lib "robo_cam") (part "CMP-001-000526-11"))
    )
    (comp (ref "R54")
      (value "10k")
      (footprint "RES_0201_UN1Q")
      (description "RES")
      (fields (field (name "PART NUMBER") "RC0201FR-0710KL") (field (name "MANUFACTURER") "YAGEO"))
      (libsource (lib "robo_cam") (part "CMP-001-000446-13"))
    )
    (comp (ref "R55")
      (value "121k")
      (footprint "RES_0201_UN1Q")
      (description "RES")
      (fields (field (name "TOLERANCE") "1%") (field (name "MANUFACTURER") "YAGEO"))
      (libsource (lib "robo_cam") (part "CMP-001-001157-2"))
    )
    (comp (ref "R56")
      (value "7k15")
      (footprint "RES_0201_UN1Q")
      (description "RES")
      (fields (field (name "MANUFACTURER") "YAGEO") (field (name "PART NUMBER") "RC0201FR-077K15L"))
      (libsource (lib "robo_cam") (part "CMP-001-001156-2"))
    )
    (comp (ref "R57")
      (value "52k3")
      (footprint "RES_0201_UN1Q")
      (description "RES")
      (fields (field (name "TOLERANCE") "1%") (field (name "MANUFACTURER") "YAGEO"))
      (libsource (lib "robo_cam") (part "CMP-001-001154-3"))
    )
    (comp (ref "R58")
      (value "100k")
      (footprint "RES_0201_UN1Q")
      (description "RES")
      (fields (field (name "TOLERANCE") "1%") (field (name "PART NUMBER") "RC0201FR-07100KL"))
      (libsource (lib "robo_cam") (part "CMP-001-000526-11"))
    )
    (comp (ref "R59")
      (value "100k")
      (footprint "RES_0201_UN1Q")
      (description "RES")
      (fields (field (name "TOLERANCE") "1%") (field (name "PART NUMBER") "RC0201FR-07100KL"))
      (libsource (lib "robo_cam") (part "CMP-001-000526-11"))
    )
    (comp (ref "R60")
      (value "9k76")
      (footprint "RES_0201_UN1Q")
      (description "RES")
      (fields (field (name "PART NUMBER") "RC0201FR-079K76L") (field (name "TOLERANCE") "1%"))
      (libsource (lib "robo_cam") (part "CMP-001-001155-2"))
    )
    (comp (ref "R61")
      (value "12k4")
      (footprint "RES_0201_UN1Q")
      (description "RES")
      (fields (field (name "TOLERANCE") "1%") (field (name "MANUFACTURER") "YAGEO"))
      (libsource (lib "robo_cam") (part "CMP-001-000535-12"))
    )
    (comp (ref "R62")
      (value "10k")
      (footprint "RES_0201_UN1Q")
      (description "RES")
      (fields (field (name "PART NUMBER") "RC0201FR-0710KL") (field (name "MANUFACTURER") "YAGEO"))
      (libsource (lib "robo_cam") (part "CMP-001-000446-13"))
    )
    (comp (ref "R63")
      (value "121k")
      (footprint "RES_0201_UN1Q")
      (description "RES")
      (fields (field (name "TOLERANCE") "1%") (field (name "MANUFACTURER") "YAGEO"))
      (libsource (lib "robo_cam") (part "CMP-001-001157-2"))
    )
    (comp (ref "R64")
      (value "7k15")
      (footprint "RES_0201_UN1Q")
      (description "RES")
      (fields (field (name "MANUFACTURER") "YAGEO") (field (name "PART NUMBER") "RC0201FR-077K15L"))
      (libsource (lib "robo_cam") (part "CMP-001-001156-2"))
    )
    (comp (ref "R65")
      (value "42k2")
      (footprint "RES_0201_UN1Q")
      (description "RES")
      (fields (field (name "TOLERANCE") "1%") (field (name "MANUFACTURER") "YAGEO"))
      (libsource (lib "CM5_library") (part "CMP-001-001160-1"))
    )
    (comp (ref "R66")
      (value "40k2")
      (footprint "RES_0201_UN1Q")
      (description "RES")
      (fields (field (name "PART NUMBER") "RC0201FR-0740K2L") (field (name "TOLERANCE") "1%"))
      (libsource (lib "CM5_library") (part "CMP-001-001257-9"))
    )
    (comp (ref "R67")
      (value "100k")
      (footprint "RES_0201_UN1Q")
      (description "RES")
      (fields (field (name "TOLERANCE") "1%") (field (name "PART NUMBER") "RC0201FR-07100KL"))
      (libsource (lib "robo_cam") (part "CMP-001-000526-11"))
    )
    (comp (ref "R68")
      (value "100k")
      (footprint "RES_0201_UN1Q")
      (description "RES")
      (fields (field (name "TOLERANCE") "1%") (field (name "PART NUMBER") "RC0201FR-07100KL"))
      (libsource (lib "robo_cam") (part "CMP-001-000526-11"))
    )
    (comp (ref "R69")
      (value "13k3")
      (footprint "RES_0201_UN1Q")
      (description "RES")
      (fields (field (name "PART NUMBER") "RC0201FR-0713K3L") (field (name "TOLERANCE") "1%"))
      (libsource (lib "CM5_library") (part "CMP-001-001161-1"))
    )
    (comp (ref "R70")
      (value "100k")
      (footprint "RES_0201_UN1Q")
      (description "RES")
      (fields (field (name "TOLERANCE") "1%") (field (name "PART NUMBER") "RC0201FR-07100KL"))
      (libsource (lib "robo_cam") (part "CMP-001-000526-11"))
    )
    (comp (ref "R71")
      (value "11k")
      (footprint "RES_0201_UN1Q")
      (description "RES")
      (fields (field (name "MANUFACTURER") "YAGEO") (field (name "PART NUMBER") "RC0201FR-0711KL"))
      (libsource (lib "CM5_library") (part "CMP-001-000449-12"))
    )
    (comp (ref "R72")
      (value "56k2")
      (footprint "RES_0201_UN1Q")
      (description "RES")
      (fields (field (name "PART NUMBER") "CRCW020156K2FNED") (field (name "MANUFACTURER") "Vishay Dale"))
      (libsource (lib "CM5_library") (part "CMP-001-001496-1"))
    )
    (comp (ref "R73")
      (value "7k15")
      (footprint "RES_0201_UN1Q")
      (description "RES")
      (fields (field (name "MANUFACTURER") "YAGEO") (field (name "PART NUMBER") "RC0201FR-077K15L"))
      (libsource (lib "robo_cam") (part "CMP-001-001156-2"))
    )
    (comp (ref "T3")
      (value "TVS_SD36C-01FTG")
      (footprint "SOD-323")
      (description "450 W bidirectional TVS diode, 36 V / 60 V")
      (fields
        (field (name "MANUFACTURER") "Littelfuse")
        (field (name "PART NUMBER") "SD36C-01FTG")
        (field (name "VOLTAGE") "60V")
        (field (name "ALTIUM_VALUE") "36V")
        (field (name "MANUFACTURER_1") "Littelfuse")
        (field (name "SOURCE") "UUDET_KOMPONENTIT.SchLib")
      )
      (libsource (lib "CM5_library") (part "CMP-001-000966-8"))
    )
    (comp (ref "U7")
      (value "TPSM64406RCHR")
      (footprint "QFN-FCMOD-28_TI")
      (description "SMPS Module,  3V to 36V Input, 0.8V to 16V Dual Output, 3A+3A")
      (fields
        (field (name "MANUFACTURER") "Texas Instruments")
        (field (name "PART NUMBER") "TPSM64406RCHR")
        (field (name "MANUFACTURER_1") "Texas Instruments")
      )
      (libsource (lib "robo_cam") (part "CMP-001-001142-13"))
    )
    (comp (ref "U8")
      (value "TPSM64406RCHR")
      (footprint "QFN-FCMOD-28_TI")
      (description "SMPS Module,  3V to 36V Input, 0.8V to 16V Dual Output, 3A+3A")
      (fields
        (field (name "MANUFACTURER") "Texas Instruments")
        (field (name "PART NUMBER") "TPSM64406RCHR")
        (field (name "MANUFACTURER_1") "Texas Instruments")
      )
      (libsource (lib "robo_cam") (part "CMP-001-001142-13"))
    )
    (comp (ref "U9")
      (value "TPSM64406RCHR")
      (footprint "QFN-FCMOD-28_TI")
      (description "SMPS Module,  3V to 36V Input, 0.8V to 16V Dual Output, 3A+3A")
      (fields
        (field (name "MANUFACTURER") "Texas Instruments")
        (field (name "PART NUMBER") "TPSM64406RCHR")
        (field (name "MANUFACTURER_1") "Texas Instruments")
      )
      (libsource (lib "robo_cam") (part "CMP-001-001142-13"))
    )
  )
  (nets
    (net (code "2") (name "/1V8_OUT_RBC") (class "Default")
      (node (ref "C186") (pin "1") (pinfunction "1_1") (pintype "passive"))
      (node (ref "C187") (pin "1") (pinfunction "1_1") (pintype "passive"))
      (node (ref "C188") (pin "1") (pinfunction "1_1") (pintype "passive"))
      (node (ref "C189") (pin "1") (pinfunction "1_1") (pintype "passive"))
      (node (ref "C190") (pin "1") (pinfunction "1_1") (pintype "passive"))
      (node (ref "C192") (pin "1") (pinfunction "1_1") (pintype "passive"))
      (node (ref "L18") (pin "1") (pinfunction "1_1") (pintype "passive"))
      (node (ref "PTP70") (pin "1") (pinfunction "TP_1") (pintype "passive"))
      (node (ref "R61") (pin "2") (pinfunction "2_2") (pintype "passive"))
      (node (ref "U8") (pin "18") (pinfunction "VOUT2_18") (pintype "power_in"))
      (node (ref "U8") (pin "19") (pinfunction "VOUT2_19") (pintype "power_in"))
      (node (ref "U8") (pin "9") (pinfunction "COMP_VOSNS2_9") (pintype "passive"))
    )
    (net (code "3") (name "/3V3_OUT") (class "Default")
      (node (ref "C160") (pin "1") (pinfunction "1_1") (pintype "passive"))
      (node (ref "C161") (pin "1") (pinfunction "1_1") (pintype "passive"))
      (node (ref "C162") (pin "1") (pinfunction "1_1") (pintype "passive"))
      (node (ref "C163") (pin "1") (pinfunction "1_1") (pintype "passive"))
      (node (ref "C164") (pin "1") (pinfunction "1_1") (pintype "passive"))
      (node (ref "C166") (pin "1") (pinfunction "1_1") (pintype "passive"))
      (node (ref "L13") (pin "1") (pinfunction "1_1") (pintype "passive"))
      (node (ref "PTP57") (pin "1") (pinfunction "TP_1") (pintype "passive"))
      (node (ref "R52") (pin "1") (pinfunction "1_1") (pintype "passive"))
      (node (ref "U7") (pin "18") (pinfunction "VOUT2_18") (pintype "power_in"))
      (node (ref "U7") (pin "19") (pinfunction "VOUT2_19") (pintype "power_in"))
      (node (ref "U7") (pin "9") (pinfunction "COMP_VOSNS2_9") (pintype "passive"))
    )
    (net (code "4") (name "/5V0_OUT") (class "Default")
      (node (ref "C143") (pin "1") (pinfunction "1_1") (pintype "passive"))
      (node (ref "C144") (pin "1") (pinfunction "1_1") (pintype "passive"))
      (node (ref "C145") (pin "1") (pinfunction "1_1") (pintype "passive"))
      (node (ref "C146") (pin "1") (pinfunction "1_1") (pintype "passive"))
      (node (ref "C147") (pin "1") (pinfunction "1_1") (pintype "passive"))
      (node (ref "C159") (pin "1") (pinfunction "1_1") (pintype "passive"))
      (node (ref "L10") (pin "1") (pinfunction "1_1") (pintype "passive"))
      (node (ref "PTP48") (pin "1") (pinfunction "TP_1") (pintype "passive"))
      (node (ref "R48") (pin "2") (pinfunction "2_2") (pintype "passive"))
      (node (ref "U7") (pin "20") (pinfunction "VOUT1_20") (pintype "power_in"))
      (node (ref "U7") (pin "21") (pinfunction "VOUT1_21") (pintype "power_in"))
      (node (ref "U7") (pin "3") (pinfunction "VOSNS1_3") (pintype "passive"))
    )
    (net (code "5") (name "/5V0_OUT_RBC") (class "Default")
      (node (ref "C175") (pin "1") (pinfunction "1_1") (pintype "passive"))
      (node (ref "C176") (pin "1") (pinfunction "1_1") (pintype "passive"))
      (node (ref "C177") (pin "1") (pinfunction "1_1") (pintype "passive"))
      (node (ref "C178") (pin "1") (pinfunction "1_1") (pintype "passive"))
      (node (ref "C179") (pin "1") (pinfunction "1_1") (pintype "passive"))
      (node (ref "C185") (pin "1") (pinfunction "1_1") (pintype "passive"))
      (node (ref "L16") (pin "1") (pinfunction "1_1") (pintype "passive"))
      (node (ref "PTP64") (pin "1") (pinfunction "TP_1") (pintype "passive"))
      (node (ref "R57") (pin "2") (pinfunction "2_2") (pintype "passive"))
      (node (ref "U8") (pin "20") (pinfunction "VOUT1_20") (pintype "power_in"))
      (node (ref "U8") (pin "21") (pinfunction "VOUT1_21") (pintype "power_in"))
      (node (ref "U8") (pin "3") (pinfunction "VOSNS1_3") (pintype "passive"))
    )
    (net (code "6") (name "/ADJ_mPCIe_PWR") (class "Default")
      (node (ref "PTP78") (pin "1") (pinfunction "TP_1") (pintype "passive"))
      (node (ref "Q1") (pin "1") (pinfunction "G_1") (pintype "passive"))
      (node (ref "R70") (pin "2") (pinfunction "2_2") (pintype "passive"))
    )
    (net (code "7") (name "/EN_SMPS_RBC") (class "Default")
      (node (ref "U8") (pin "2") (pinfunction "EN1_2") (pintype "input"))
    )
    (net (code "8") (name "/EN_mPCIe_PWR") (class "Default")
      (node (ref "U9") (pin "10") (pinfunction "EN2_10") (pintype "input"))
      (node (ref "U9") (pin "2") (pinfunction "EN1_2") (pintype "input"))
    )
    (net (code "10") (name "/PGOOD_3V3") (class "Default")
      (node (ref "PTP55") (pin "1") (pinfunction "TP_1") (pintype "passive"))
      (node (ref "R49") (pin "1") (pinfunction "1_1") (pintype "passive"))
      (node (ref "U7") (pin "12") (pinfunction "SYNCOUT_PG2_12") (pintype "passive"))
    )
    (net (code "11") (name "/PGOOD_5V0") (class "Default")
      (node (ref "PTP53") (pin "1") (pinfunction "TP_1") (pintype "passive"))
      (node (ref "R50") (pin "1") (pinfunction "1_1") (pintype "passive"))
      (node (ref "U7") (pin "1") (pinfunction "PG1_1") (pintype "passive"))
      (node (ref "U7") (pin "10") (pinfunction "EN2_10") (pintype "input"))
    )
    (net (code "12") (name "/PGOOD_RBC_1V8") (class "Default")
      (node (ref "PTP68") (pin "1") (pinfunction "TP_1") (pintype "passive"))
      (node (ref "R58") (pin "1") (pinfunction "1_1") (pintype "passive"))
      (node (ref "U8") (pin "12") (pinfunction "SYNCOUT_PG2_12") (pintype "passive"))
    )
    (net (code "13") (name "/PGOOD_RBC_5V0") (class "Default")
      (node (ref "PTP66") (pin "1") (pinfunction "TP_1") (pintype "passive"))
      (node (ref "R59") (pin "1") (pinfunction "1_1") (pintype "passive"))
      (node (ref "U8") (pin "1") (pinfunction "PG1_1") (pintype "passive"))
      (node (ref "U8") (pin "10") (pinfunction "EN2_10") (pintype "input"))
    )
    (net (code "14") (name "/PGOOD_mPCIe") (class "Default")
      (node (ref "PTP79") (pin "1") (pinfunction "TP_1") (pintype "passive"))
      (node (ref "R68") (pin "1") (pinfunction "1_1") (pintype "passive"))
      (node (ref "U9") (pin "1") (pinfunction "PG1_1") (pintype "passive"))
    )
    (net (code "15") (name "/RF1_OUT") (class "Default")
      (node (ref "C193") (pin "1") (pinfunction "1_1") (pintype "passive"))
      (node (ref "C194") (pin "1") (pinfunction "1_1") (pintype "passive"))
      (node (ref "C195") (pin "1") (pinfunction "1_1") (pintype "passive"))
      (node (ref "C196") (pin "1") (pinfunction "1_1") (pintype "passive"))
      (node (ref "C197") (pin "1") (pinfunction "1_1") (pintype "passive"))
      (node (ref "C211") (pin "1") (pinfunction "1_1") (pintype "passive"))
      (node (ref "C212") (pin "1") (pinfunction "1_1") (pintype "passive"))
      (node (ref "C213") (pin "1") (pinfunction "1_1") (pintype "passive"))
      (node (ref "C214") (pin "1") (pinfunction "1_1") (pintype "passive"))
      (node (ref "C215") (pin "1") (pinfunction "1_1") (pintype "passive"))
      (node (ref "C216") (pin "1") (pinfunction "1_1") (pintype "passive"))
      (node (ref "L19") (pin "1") (pinfunction "1_1") (pintype "passive"))
      (node (ref "PTP74") (pin "1") (pinfunction "TP_1") (pintype "passive"))
      (node (ref "PTP82") (pin "1") (pinfunction "TP_1") (pintype "passive"))
      (node (ref "R65") (pin "2") (pinfunction "2_2") (pintype "passive"))
      (node (ref "U9") (pin "18") (pinfunction "VOUT2_18") (pintype "power_in"))
      (node (ref "U9") (pin "19") (pinfunction "VOUT2_19") (pintype "power_in"))
      (node (ref "U9") (pin "20") (pinfunction "VOUT1_20") (pintype "power_in"))
      (node (ref "U9") (pin "21") (pinfunction "VOUT1_21") (pintype "power_in"))
      (node (ref "U9") (pin "3") (pinfunction "VOSNS1_3") (pintype "passive"))
    )
    (net (code "16") (name "/VCC_LDO1") (class "Default")
      (node (ref "C152") (pin "1") (pinfunction "1_1") (pintype "passive"))
      (node (ref "PTP50") (pin "1") (pinfunction "TP_1") (pintype "passive"))
      (node (ref "R49") (pin "2") (pinfunction "2_2") (pintype "passive"))
      (node (ref "R50") (pin "2") (pinfunction "2_2") (pintype "passive"))
      (node (ref "U7") (pin "27") (pinfunction "SYNC_27") (pintype "input"))
      (node (ref "U7") (pin "5") (pinfunction "VCC_5") (pintype "power_in"))
    )
    (net (code "17") (name "/VCC_LDO3") (class "Default")
      (node (ref "C184") (pin "1") (pinfunction "1_1") (pintype "passive"))
      (node (ref "PTP65") (pin "1") (pinfunction "TP_1") (pintype "passive"))
      (node (ref "R58") (pin "2") (pinfunction "2_2") (pintype "passive"))
      (node (ref "R59") (pin "2") (pinfunction "2_2") (pintype "passive"))
      (node (ref "U8") (pin "27") (pinfunction "SYNC_27") (pintype "input"))
      (node (ref "U8") (pin "5") (pinfunction "VCC_5") (pintype "power_in"))
    )
    (net (code "18") (name "/VIN1_5V0") (class "Default")
      (node (ref "C141") (pin "2") (pinfunction "2_2") (pintype "passive"))
      (node (ref "C142") (pin "1") (pinfunction "1_1") (pintype "passive"))
      (node (ref "L9") (pin "2") (pinfunction "2_2") (pintype "passive"))
      (node (ref "PTP46") (pin "1") (pinfunction "TP_1") (pintype "passive"))
      (node (ref "U7") (pin "25") (pinfunction "VIN1_25") (pintype "power_in"))
    )
    (net (code "19") (name "/VIN1_5V0_RBC") (class "Default")
      (node (ref "C173") (pin "2") (pinfunction "2_2") (pintype "passive"))
      (node (ref "C174") (pin "2") (pinfunction "2_2") (pintype "passive"))
      (node (ref "L15") (pin "2") (pinfunction "2_2") (pintype "passive"))
      (node (ref "PTP62") (pin "1") (pinfunction "TP_1") (pintype "passive"))
      (node (ref "U8") (pin "25") (pinfunction "VIN1_25") (pintype "power_in"))
    )
    (net (code "20") (name "/VIN1_smps1") (class "Default")
      (node (ref "C205") (pin "2") (pinfunction "2_2") (pintype "passive"))
      (node (ref "C206") (pin "2") (pinfunction "2_2") (pintype "passive"))
      (node (ref "L20") (pin "2") (pinfunction "2_2") (pintype "passive"))
      (node (ref "PTP75") (pin "1") (pinfunction "TP_1") (pintype "passive"))
      (node (ref "U9") (pin "25") (pinfunction "VIN1_25") (pintype "power_in"))
    )
    (net (code "21") (name "/VIN2_3V3") (class "Default")
      (node (ref "C150") (pin "2") (pinfunction "2_2") (pintype "passive"))
      (node (ref "C151") (pin "1") (pinfunction "1_1") (pintype "passive"))
      (node (ref "L11") (pin "2") (pinfunction "2_2") (pintype "passive"))
      (node (ref "PTP52") (pin "1") (pinfunction "TP_1") (pintype "passive"))
      (node (ref "U7") (pin "14") (pinfunction "VIN2_14") (pintype "power_in"))
    )
    (net (code "22") (name "/VIN2_3V3_RBC") (class "Default")
      (node (ref "C182") (pin "2") (pinfunction "2_2") (pintype "passive"))
      (node (ref "C183") (pin "2") (pinfunction "2_2") (pintype "passive"))
      (node (ref "L17") (pin "2") (pinfunction "2_2") (pintype "passive"))
      (node (ref "U8") (pin "14") (pinfunction "VIN2_14") (pintype "power_in"))
    )
    (net (code "23") (name "/VIN2_smps1") (class "Default")
      (node (ref "C208") (pin "2") (pinfunction "2_2") (pintype "passive"))
      (node (ref "C209") (pin "2") (pinfunction "2_2") (pintype "passive"))
      (node (ref "L22") (pin "2") (pinfunction "2_2") (pintype "passive"))
      (node (ref "U9") (pin "14") (pinfunction "VIN2_14") (pintype "power_in"))
    )
    (net (code "27") (name "/smps1_LDO") (class "Default")
      (node (ref "C210") (pin "1") (pinfunction "1_1") (pintype "passive"))
      (node (ref "PTP77") (pin "1") (pinfunction "TP_1") (pintype "passive"))
      (node (ref "R67") (pin "2") (pinfunction "2_2") (pintype "passive"))
      (node (ref "R68") (pin "2") (pinfunction "2_2") (pintype "passive"))
      (node (ref "U9") (pin "27") (pinfunction "SYNC_27") (pintype "input"))
      (node (ref "U9") (pin "5") (pinfunction "VCC_5") (pintype "power_in"))
    )
    (net (code "29") (name "1V8_PER") (class "Default")
      (node (ref "C191") (pin "2") (pinfunction "2_2") (pintype "passive"))
      (node (ref "L18") (pin "2") (pinfunction "2_2") (pintype "passive"))
      (node (ref "PTP69") (pin "1") (pinfunction "TP_1") (pintype "passive"))
    )
    (net (code "30") (name "3V3_SMPS") (class "Default")
      (node (ref "C165") (pin "2") (pinfunction "2_2") (pintype "passive"))
      (node (ref "L13") (pin "2") (pinfunction "2_2") (pintype "passive"))
      (node (ref "PTP56") (pin "1") (pinfunction "TP_1") (pintype "passive"))
    )
    (net (code "31") (name "5V0_SMPS") (class "Default")
      (node (ref "C148") (pin "2") (pinfunction "2_2") (pintype "passive"))
      (node (ref "L10") (pin "2") (pinfunction "2_2") (pintype "passive"))
      (node (ref "PTP47") (pin "1") (pinfunction "TP_1") (pintype "passive"))
    )
    (net (code "32") (name "5V0_SMPS_RBC") (class "Default")
      (node (ref "C180") (pin "2") (pinfunction "2_2") (pintype "passive"))
      (node (ref "L16") (pin "2") (pinfunction "2_2") (pintype "passive"))
      (node (ref "PTP63") (pin "1") (pinfunction "TP_1") (pintype "passive"))
    )
    (net (code "33") (name "GND") (class "Default")
      (node (ref "C141") (pin "1") (pinfunction "1_1") (pintype "passive"))
      (node (ref "C142") (pin "2") (pinfunction "2_2") (pintype "passive"))
      (node (ref "C143") (pin "2") (pinfunction "2_2") (pintype "passive"))
      (node (ref "C144") (pin "2") (pinfunction "2_2") (pintype "passive"))
      (node (ref "C145") (pin "2") (pinfunction "2_2") (pintype "passive"))
      (node (ref "C146") (pin "2") (pinfunction "2_2") (pintype "passive"))
      (node (ref "C147") (pin "2") (pinfunction "2_2") (pintype "passive"))
      (node (ref "C148") (pin "1") (pinfunction "1_1") (pintype "passive"))
      (node (ref "C149") (pin "2") (pinfunction "2_2") (pintype "passive"))
      (node (ref "C150") (pin "1") (pinfunction "1_1") (pintype "passive"))
      (node (ref "C151") (pin "2") (pinfunction "2_2") (pintype "passive"))
      (node (ref "C152") (pin "2") (pinfunction "2_2") (pintype "passive"))
      (node (ref "C153") (pin "1") (pinfunction "1_1") (pintype "passive"))
      (node (ref "C154") (pin "1") (pinfunction "1_1") (pintype "passive"))
      (node (ref "C155") (pin "2") (pinfunction "2_2") (pintype "passive"))
      (node (ref "C156") (pin "2") (pinfunction "2_2") (pintype "passive"))
      (node (ref "C157") (pin "1") (pinfunction "1_1") (pintype "passive"))
      (node (ref "C158") (pin "1") (pinfunction "1_1") (pintype "passive"))
      (node (ref "C159") (pin "2") (pinfunction "2_2") (pintype "passive"))
      (node (ref "C160") (pin "2") (pinfunction "2_2") (pintype "passive"))
      (node (ref "C161") (pin "2") (pinfunction "2_2") (pintype "passive"))
      (node (ref "C162") (pin "2") (pinfunction "2_2") (pintype "passive"))
      (node (ref "C163") (pin "2") (pinfunction "2_2") (pintype "passive"))
      (node (ref "C164") (pin "2") (pinfunction "2_2") (pintype "passive"))
      (node (ref "C165") (pin "1") (pinfunction "1_1") (pintype "passive"))
      (node (ref "C166") (pin "2") (pinfunction "2_2") (pintype "passive"))
      (node (ref "C167") (pin "1") (pinfunction "1_1") (pintype "passive"))
      (node (ref "C168") (pin "1") (pinfunction "1_1") (pintype "passive"))
      (node (ref "C169") (pin "2") (pinfunction "2_2") (pintype "passive"))
      (node (ref "C170") (pin "2") (pinfunction "2_2") (pintype "passive"))
      (node (ref "C171") (pin "1") (pinfunction "1_1") (pintype "passive"))
      (node (ref "C172") (pin "1") (pinfunction "1_1") (pintype "passive"))
      (node (ref "C173") (pin "1") (pinfunction "1_1") (pintype "passive"))
      (node (ref "C174") (pin "1") (pinfunction "1_1") (pintype "passive"))
      (node (ref "C175") (pin "2") (pinfunction "2_2") (pintype "passive"))
      (node (ref "C176") (pin "2") (pinfunction "2_2") (pintype "passive"))
      (node (ref "C177") (pin "2") (pinfunction "2_2") (pintype "passive"))
      (node (ref "C178") (pin "2") (pinfunction "2_2") (pintype "passive"))
      (node (ref "C179") (pin "2") (pinfunction "2_2") (pintype "passive"))
      (node (ref "C180") (pin "1") (pinfunction "1_1") (pintype "passive"))
      (node (ref "C181") (pin "2") (pinfunction "2_2") (pintype "passive"))
      (node (ref "C182") (pin "1") (pinfunction "1_1") (pintype "passive"))
      (node (ref "C183") (pin "1") (pinfunction "1_1") (pintype "passive"))
      (node (ref "C184") (pin "2") (pinfunction "2_2") (pintype "passive"))
      (node (ref "C185") (pin "2") (pinfunction "2_2") (pintype "passive"))
      (node (ref "C186") (pin "2") (pinfunction "2_2") (pintype "passive"))
      (node (ref "C187") (pin "2") (pinfunction "2_2") (pintype "passive"))
      (node (ref "C188") (pin "2") (pinfunction "2_2") (pintype "passive"))
      (node (ref "C189") (pin "2") (pinfunction "2_2") (pintype "passive"))
      (node (ref "C190") (pin "2") (pinfunction "2_2") (pintype "passive"))
      (node (ref "C191") (pin "1") (pinfunction "1_1") (pintype "passive"))
      (node (ref "C192") (pin "2") (pinfunction "2_2") (pintype "passive"))
      (node (ref "C193") (pin "2") (pinfunction "2_2") (pintype "passive"))
      (node (ref "C194") (pin "2") (pinfunction "2_2") (pintype "passive"))
      (node (ref "C195") (pin "2") (pinfunction "2_2") (pintype "passive"))
      (node (ref "C196") (pin "2") (pinfunction "2_2") (pintype "passive"))
      (node (ref "C197") (pin "2") (pinfunction "2_2") (pintype "passive"))
      (node (ref "C198") (pin "1") (pinfunction "1_1") (pintype "passive"))
      (node (ref "C199") (pin "1") (pinfunction "1_1") (pintype "passive"))
      (node (ref "C200") (pin "1") (pinfunction "1_1") (pintype "passive"))
      (node (ref "C201") (pin "2") (pinfunction "2_2") (pintype "passive"))
      (node (ref "C202") (pin "2") (pinfunction "2_2") (pintype "passive"))
      (node (ref "C203") (pin "1") (pinfunction "1_1") (pintype "passive"))
      (node (ref "C204") (pin "1") (pinfunction "1_1") (pintype "passive"))
      (node (ref "C205") (pin "1") (pinfunction "1_1") (pintype "passive"))
      (node (ref "C206") (pin "1") (pinfunction "1_1") (pintype "passive"))
      (node (ref "C207") (pin "2") (pinfunction "2_2") (pintype "passive"))
      (node (ref "C208") (pin "1") (pinfunction "1_1") (pintype "passive"))
      (node (ref "C209") (pin "1") (pinfunction "1_1") (pintype "passive"))
      (node (ref "C210") (pin "2") (pinfunction "2_2") (pintype "passive"))
      (node (ref "C211") (pin "2") (pinfunction "2_2") (pintype "passive"))
      (node (ref "C212") (pin "2") (pinfunction "2_2") (pintype "passive"))
      (node (ref "C213") (pin "2") (pinfunction "2_2") (pintype "passive"))
      (node (ref "C214") (pin "2") (pinfunction "2_2") (pintype "passive"))
      (node (ref "C215") (pin "2") (pinfunction "2_2") (pintype "passive"))
      (node (ref "C216") (pin "2") (pinfunction "2_2") (pintype "passive"))
      (node (ref "C217") (pin "2") (pinfunction "2_2") (pintype "passive"))
      (node (ref "C218") (pin "1") (pinfunction "1_1") (pintype "passive"))
      (node (ref "C219") (pin "2") (pinfunction "2_2") (pintype "passive"))
      (node (ref "J5") (pin "1") (pinfunction "TP_1") (pintype "passive"))
      (node (ref "J6") (pin "2") (pinfunction "2_2") (pintype "passive"))
      (node (ref "J6") (pin "3") (pinfunction "3_3") (pintype "passive"))
      (node (ref "Q1") (pin "2") (pinfunction "S_2") (pintype "passive"))
      (node (ref "R51") (pin "2") (pinfunction "2_2") (pintype "passive"))
      (node (ref "R54") (pin "2") (pinfunction "2_2") (pintype "passive"))
      (node (ref "R55") (pin "1") (pinfunction "1_1") (pintype "passive"))
      (node (ref "R56") (pin "1") (pinfunction "1_1") (pintype "passive"))
      (node (ref "R60") (pin "2") (pinfunction "2_2") (pintype "passive"))
      (node (ref "R62") (pin "1") (pinfunction "1_1") (pintype "passive"))
      (node (ref "R63") (pin "1") (pinfunction "1_1") (pintype "passive"))
      (node (ref "R64") (pin "1") (pinfunction "1_1") (pintype "passive"))
      (node (ref "R69") (pin "1") (pinfunction "1_1") (pintype "passive"))
      (node (ref "R70") (pin "1") (pinfunction "1_1") (pintype "passive"))
      (node (ref "R72") (pin "1") (pinfunction "1_1") (pintype "passive"))
      (node (ref "R73") (pin "1") (pinfunction "1_1") (pintype "passive"))
      (node (ref "T3") (pin "2") (pinfunction "2_2") (pintype "passive"))
      (node (ref "U7") (pin "13") (pinfunction "PGND2_13") (pintype "power_in"))
      (node (ref "U7") (pin "26") (pinfunction "PGND1_26") (pintype "power_in"))
      (node (ref "U7") (pin "28") (pinfunction "EP_28") (pintype "power_in"))
      (node (ref "U7") (pin "6") (pinfunction "AGND_6") (pintype "power_in"))
      (node (ref "U8") (pin "13") (pinfunction "PGND2_13") (pintype "power_in"))
      (node (ref "U8") (pin "26") (pinfunction "PGND1_26") (pintype "power_in"))
      (node (ref "U8") (pin "28") (pinfunction "EP_28") (pintype "power_in"))
      (node (ref "U8") (pin "6") (pinfunction "AGND_6") (pintype "power_in"))
      (node (ref "U9") (pin "13") (pinfunction "PGND2_13") (pintype "power_in"))
      (node (ref "U9") (pin "26") (pinfunction "PGND1_26") (pintype "power_in"))
      (node (ref "U9") (pin "28") (pinfunction "EP_28") (pintype "power_in"))
      (node (ref "U9") (pin "6") (pinfunction "AGND_6") (pintype "power_in"))
    )
    (net (code "34") (name "Net-(C218-Pad2)") (class "Default")
      (node (ref "C218") (pin "2") (pinfunction "2_2") (pintype "passive"))
      (node (ref "R71") (pin "2") (pinfunction "2_2") (pintype "passive"))
    )
    (net (code "35") (name "Net-(CR1-ANODE)") (class "Default")
      (node (ref "CR1") (pin "2") (pinfunction "ANODE_2") (pintype "passive"))
      (node (ref "F1") (pin "2") (pinfunction "2_2") (pintype "passive"))
    )
    (net (code "36") (name "Net-(F1-Pad1)") (class "Default")
      (node (ref "F1") (pin "1") (pinfunction "1_1") (pintype "passive"))
      (node (ref "J6") (pin "1A") (pinfunction "1_1A") (pintype "passive"))
      (node (ref "J6") (pin "1B") (pinfunction "1_1B") (pintype "passive"))
      (node (ref "T3") (pin "1") (pinfunction "1_1") (pintype "passive"))
    )
    (net (code "37") (name "Net-(PTP54-TP)") (class "Default")
      (node (ref "PTP54") (pin "1") (pinfunction "TP_1") (pintype "passive"))
      (node (ref "R48") (pin "1") (pinfunction "1_1") (pintype "passive"))
      (node (ref "R51") (pin "1") (pinfunction "1_1") (pintype "passive"))
      (node (ref "U7") (pin "4") (pinfunction "FB1_4") (pintype "passive"))
    )
    (net (code "38") (name "Net-(PTP58-TP)") (class "Default")
      (node (ref "PTP58") (pin "1") (pinfunction "TP_1") (pintype "passive"))
      (node (ref "R53") (pin "1") (pinfunction "1_1") (pintype "passive"))
      (node (ref "U7") (pin "2") (pinfunction "EN1_2") (pintype "input"))
    )
    (net (code "39") (name "Net-(PTP61-TP)") (class "Default")
      (node (ref "PTP61") (pin "1") (pinfunction "TP_1") (pintype "passive"))
      (node (ref "R52") (pin "2") (pinfunction "2_2") (pintype "passive"))
      (node (ref "R54") (pin "1") (pinfunction "1_1") (pintype "passive"))
      (node (ref "U7") (pin "8") (pinfunction "SS_FB2_8") (pintype "passive"))
    )
    (net (code "40") (name "Net-(PTP67-TP)") (class "Default")
      (node (ref "PTP67") (pin "1") (pinfunction "TP_1") (pintype "passive"))
      (node (ref "R57") (pin "1") (pinfunction "1_1") (pintype "passive"))
      (node (ref "R60") (pin "1") (pinfunction "1_1") (pintype "passive"))
      (node (ref "U8") (pin "4") (pinfunction "FB1_4") (pintype "passive"))
    )
    (net (code "41") (name "Net-(PTP71-TP)") (class "Default")
      (node (ref "PTP71") (pin "1") (pinfunction "TP_1") (pintype "passive"))
      (node (ref "R61") (pin "1") (pinfunction "1_1") (pintype "passive"))
      (node (ref "R62") (pin "2") (pinfunction "2_2") (pintype "passive"))
      (node (ref "U8") (pin "8") (pinfunction "SS_FB2_8") (pintype "passive"))
    )
    (net (code "42") (name "Net-(PTP80-TP)") (class "Default")
      (node (ref "PTP80") (pin "1") (pinfunction "TP_1") (pintype "passive"))
      (node (ref "R65") (pin "1") (pinfunction "1_1") (pintype "passive"))
      (node (ref "R66") (pin "1") (pinfunction "1_1") (pintype "passive"))
      (node (ref "R69") (pin "2") (pinfunction "2_2") (pintype "passive"))
      (node (ref "U9") (pin "4") (pinfunction "FB1_4") (pintype "passive"))
    )
    (net (code "43") (name "Net-(PTP81-TP)") (class "Default")
      (node (ref "PTP81") (pin "1") (pinfunction "TP_1") (pintype "passive"))
      (node (ref "R67") (pin "1") (pinfunction "1_1") (pintype "passive"))
      (node (ref "U9") (pin "12") (pinfunction "SYNCOUT_PG2_12") (pintype "passive"))
    )
    (net (code "44") (name "Net-(PTP83-TP)") (class "Default")
      (node (ref "PTP83") (pin "1") (pinfunction "TP_1") (pintype "passive"))
      (node (ref "R72") (pin "2") (pinfunction "2_2") (pintype "passive"))
      (node (ref "U9") (pin "11") (pinfunction "CONFIG_11") (pintype "passive"))
    )
    (net (code "45") (name "Net-(PTP84-TP)") (class "Default")
      (node (ref "PTP84") (pin "1") (pinfunction "TP_1") (pintype "passive"))
      (node (ref "R73") (pin "2") (pinfunction "2_2") (pintype "passive"))
      (node (ref "U9") (pin "7") (pinfunction "RT_7") (pintype "passive"))
    )
    (net (code "46") (name "Net-(PTP85-TP)") (class "Default")
      (node (ref "C219") (pin "1") (pinfunction "1_1") (pintype "passive"))
      (node (ref "PTP85") (pin "1") (pinfunction "TP_1") (pintype "passive"))
      (node (ref "U9") (pin "8") (pinfunction "SS_FB2_8") (pintype "passive"))
    )
    (net (code "47") (name "Net-(Q1-D)") (class "Default")
      (node (ref "Q1") (pin "3") (pinfunction "D_3") (pintype "passive"))
      (node (ref "R66") (pin "2") (pinfunction "2_2") (pintype "passive"))
    )
    (net (code "48") (name "Net-(U7-CONFIG)") (class "Default")
      (node (ref "R55") (pin "2") (pinfunction "2_2") (pintype "passive"))
      (node (ref "U7") (pin "11") (pinfunction "CONFIG_11") (pintype "passive"))
    )
    (net (code "49") (name "Net-(U7-RT)") (class "Default")
      (node (ref "R56") (pin "2") (pinfunction "2_2") (pintype "passive"))
      (node (ref "U7") (pin "7") (pinfunction "RT_7") (pintype "passive"))
    )
    (net (code "50") (name "Net-(U8-CONFIG)") (class "Default")
      (node (ref "R63") (pin "2") (pinfunction "2_2") (pintype "passive"))
      (node (ref "U8") (pin "11") (pinfunction "CONFIG_11") (pintype "passive"))
    )
    (net (code "51") (name "Net-(U8-RT)") (class "Default")
      (node (ref "R64") (pin "2") (pinfunction "2_2") (pintype "passive"))
      (node (ref "U8") (pin "7") (pinfunction "RT_7") (pintype "passive"))
    )
    (net (code "52") (name "Net-(U9-COMP_VOSNS2)") (class "Default")
      (node (ref "C217") (pin "1") (pinfunction "1_1") (pintype "passive"))
      (node (ref "R71") (pin "1") (pinfunction "1_1") (pintype "passive"))
      (node (ref "U9") (pin "9") (pinfunction "COMP_VOSNS2_9") (pintype "passive"))
    )
    (net (code "53") (name "VBUS_RBC_FILT") (class "Default")
      (node (ref "C171") (pin "2") (pinfunction "2_2") (pintype "passive"))
      (node (ref "C172") (pin "2") (pinfunction "2_2") (pintype "passive"))
      (node (ref "L14") (pin "2") (pinfunction "2_2") (pintype "passive"))
      (node (ref "PTP60") (pin "1") (pinfunction "TP_1") (pintype "passive"))
    )
    (net (code "54") (name "VBUS_RF_FILT") (class "Default")
      (node (ref "C203") (pin "2") (pinfunction "2_2") (pintype "passive"))
      (node (ref "C204") (pin "2") (pinfunction "2_2") (pintype "passive"))
      (node (ref "C207") (pin "1") (pinfunction "1_1") (pintype "passive"))
      (node (ref "L20") (pin "1") (pinfunction "1_1") (pintype "passive"))
      (node (ref "L21") (pin "2") (pinfunction "2_2") (pintype "passive"))
      (node (ref "L22") (pin "1") (pinfunction "1_1") (pintype "passive"))
      (node (ref "PTP76") (pin "1") (pinfunction "TP_1") (pintype "passive"))
    )
    (net (code "55") (name "VBUS_SMPS_FILT") (class "Default")
      (node (ref "C181") (pin "1") (pinfunction "1_1") (pintype "passive"))
      (node (ref "L15") (pin "1") (pinfunction "1_1") (pintype "passive"))
      (node (ref "L17") (pin "1") (pinfunction "1_1") (pintype "passive"))
    )
    (net (code "56") (name "VIN_SMPS") (class "Default")
      (node (ref "C153") (pin "2") (pinfunction "2_2") (pintype "passive"))
      (node (ref "C154") (pin "2") (pinfunction "2_2") (pintype "passive"))
      (node (ref "C155") (pin "1") (pinfunction "1_1") (pintype "passive"))
      (node (ref "C156") (pin "1") (pinfunction "1_1") (pintype "passive"))
      (node (ref "C167") (pin "2") (pinfunction "2_2") (pintype "passive"))
      (node (ref "C168") (pin "2") (pinfunction "2_2") (pintype "passive"))
      (node (ref "C169") (pin "1") (pinfunction "1_1") (pintype "passive"))
      (node (ref "C170") (pin "1") (pinfunction "1_1") (pintype "passive"))
      (node (ref "C199") (pin "2") (pinfunction "2_2") (pintype "passive"))
      (node (ref "C200") (pin "2") (pinfunction "2_2") (pintype "passive"))
      (node (ref "C201") (pin "1") (pinfunction "1_1") (pintype "passive"))
      (node (ref "C202") (pin "1") (pinfunction "1_1") (pintype "passive"))
      (node (ref "CR1") (pin "1") (pinfunction "CATHODE_1") (pintype "passive"))
      (node (ref "J4") (pin "1") (pinfunction "TP_1") (pintype "passive"))
      (node (ref "L12") (pin "1") (pinfunction "1_1") (pintype "passive"))
      (node (ref "L14") (pin "1") (pinfunction "1_1") (pintype "passive"))
      (node (ref "L21") (pin "1") (pinfunction "1_1") (pintype "passive"))
      (node (ref "PTP49") (pin "1") (pinfunction "TP_1") (pintype "passive"))
      (node (ref "PTP59") (pin "1") (pinfunction "TP_1") (pintype "passive"))
      (node (ref "PTP73") (pin "1") (pinfunction "TP_1") (pintype "passive"))
    )
    (net (code "57") (name "VIN_SMPS_FILT") (class "Default")
      (node (ref "C149") (pin "1") (pinfunction "1_1") (pintype "passive"))
      (node (ref "C157") (pin "2") (pinfunction "2_2") (pintype "passive"))
      (node (ref "C158") (pin "2") (pinfunction "2_2") (pintype "passive"))
      (node (ref "L11") (pin "1") (pinfunction "1_1") (pintype "passive"))
      (node (ref "L12") (pin "2") (pinfunction "2_2") (pintype "passive"))
      (node (ref "L9") (pin "1") (pinfunction "1_1") (pintype "passive"))
      (node (ref "PTP51") (pin "1") (pinfunction "TP_1") (pintype "passive"))
      (node (ref "R53") (pin "2") (pinfunction "2_2") (pintype "passive"))
    )
    (net (code "58") (name "mPCIe_SMPS_3V3") (class "Default")
      (node (ref "C198") (pin "2") (pinfunction "2_2") (pintype "passive"))
      (node (ref "L19") (pin "2") (pinfunction "2_2") (pintype "passive"))
      (node (ref "PTP72") (pin "1") (pinfunction "TP_1") (pintype "passive"))
    )
    (net (code "59") (name "unconnected-(U7-CB1-Pad24)") (class "Default")
      (node (ref "U7") (pin "24") (pinfunction "CB1_24") (pintype "power_in+no_connect"))
    )
    (net (code "60") (name "unconnected-(U7-CB2-Pad15)") (class "Default")
      (node (ref "U7") (pin "15") (pinfunction "CB2_15") (pintype "power_in+no_connect"))
    )
    (net (code "61") (name "unconnected-(U7-SW1-Pad22)") (class "Default")
      (node (ref "U7") (pin "22") (pinfunction "SW1_22") (pintype "power_in+no_connect"))
    )
    (net (code "62") (name "unconnected-(U7-SW1-Pad23)") (class "Default")
      (node (ref "U7") (pin "23") (pinfunction "SW1_23") (pintype "power_in+no_connect"))
    )
    (net (code "63") (name "unconnected-(U7-SW2-Pad16)") (class "Default")
      (node (ref "U7") (pin "16") (pinfunction "SW2_16") (pintype "power_in+no_connect"))
    )
    (net (code "64") (name "unconnected-(U7-SW2-Pad17)") (class "Default")
      (node (ref "U7") (pin "17") (pinfunction "SW2_17") (pintype "power_in+no_connect"))
    )
    (net (code "65") (name "unconnected-(U8-CB1-Pad24)") (class "Default")
      (node (ref "U8") (pin "24") (pinfunction "CB1_24") (pintype "power_in+no_connect"))
    )
    (net (code "66") (name "unconnected-(U8-CB2-Pad15)") (class "Default")
      (node (ref "U8") (pin "15") (pinfunction "CB2_15") (pintype "power_in+no_connect"))
    )
    (net (code "67") (name "unconnected-(U8-SW1-Pad22)") (class "Default")
      (node (ref "U8") (pin "22") (pinfunction "SW1_22") (pintype "power_in+no_connect"))
    )
    (net (code "68") (name "unconnected-(U8-SW1-Pad23)") (class "Default")
      (node (ref "U8") (pin "23") (pinfunction "SW1_23") (pintype "power_in+no_connect"))
    )
    (net (code "69") (name "unconnected-(U8-SW2-Pad16)") (class "Default")
      (node (ref "U8") (pin "16") (pinfunction "SW2_16") (pintype "power_in+no_connect"))
    )
    (net (code "70") (name "unconnected-(U8-SW2-Pad17)") (class "Default")
      (node (ref "U8") (pin "17") (pinfunction "SW2_17") (pintype "power_in+no_connect"))
    )
    (net (code "71") (name "unconnected-(U9-CB1-Pad24)") (class "Default")
      (node (ref "U9") (pin "24") (pinfunction "CB1_24") (pintype "power_in+no_connect"))
    )
    (net (code "72") (name "unconnected-(U9-CB2-Pad15)") (class "Default")
      (node (ref "U9") (pin "15") (pinfunction "CB2_15") (pintype "power_in+no_connect"))
    )
    (net (code "73") (name "unconnected-(U9-SW1-Pad22)") (class "Default")
      (node (ref "U9") (pin "22") (pinfunction "SW1_22") (pintype "power_in+no_connect"))
    )
    (net (code "74") (name "unconnected-(U9-SW1-Pad23)") (class "Default")
      (node (ref "U9") (pin "23") (pinfunction "SW1_23") (pintype "power_in+no_connect"))
    )
    (net (code "75") (name "unconnected-(U9-SW2-Pad16)") (class "Default")
      (node (ref "U9") (pin "16") (pinfunction "SW2_16") (pintype "power_in+no_connect"))
    )
    (net (code "76") (name "unconnected-(U9-SW2-Pad17)") (class "Default")
      (node (ref "U9") (pin "17") (pinfunction "SW2_17") (pintype "power_in+no_connect"))
    )
  )
)
